# PFC_Interleaved_V8_1.net
KiCad netlist of a schematic drawn in Altium Designer
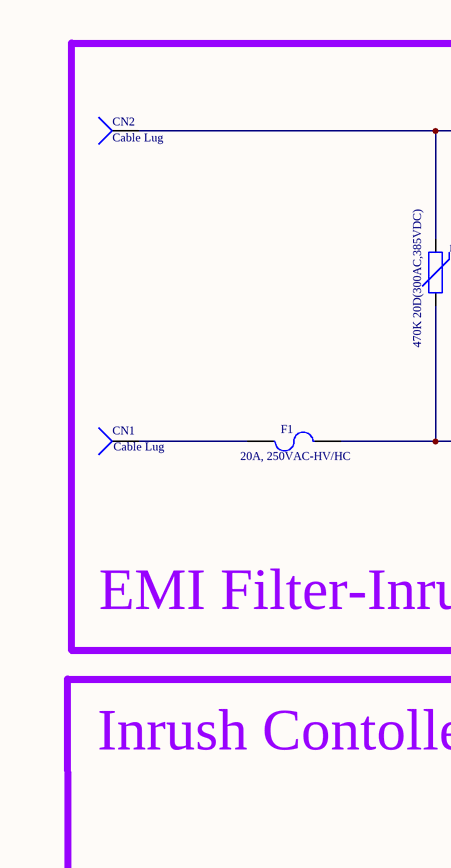
[diagram p0: PFC_Interleaved_V8.1.SchDoc, top left]
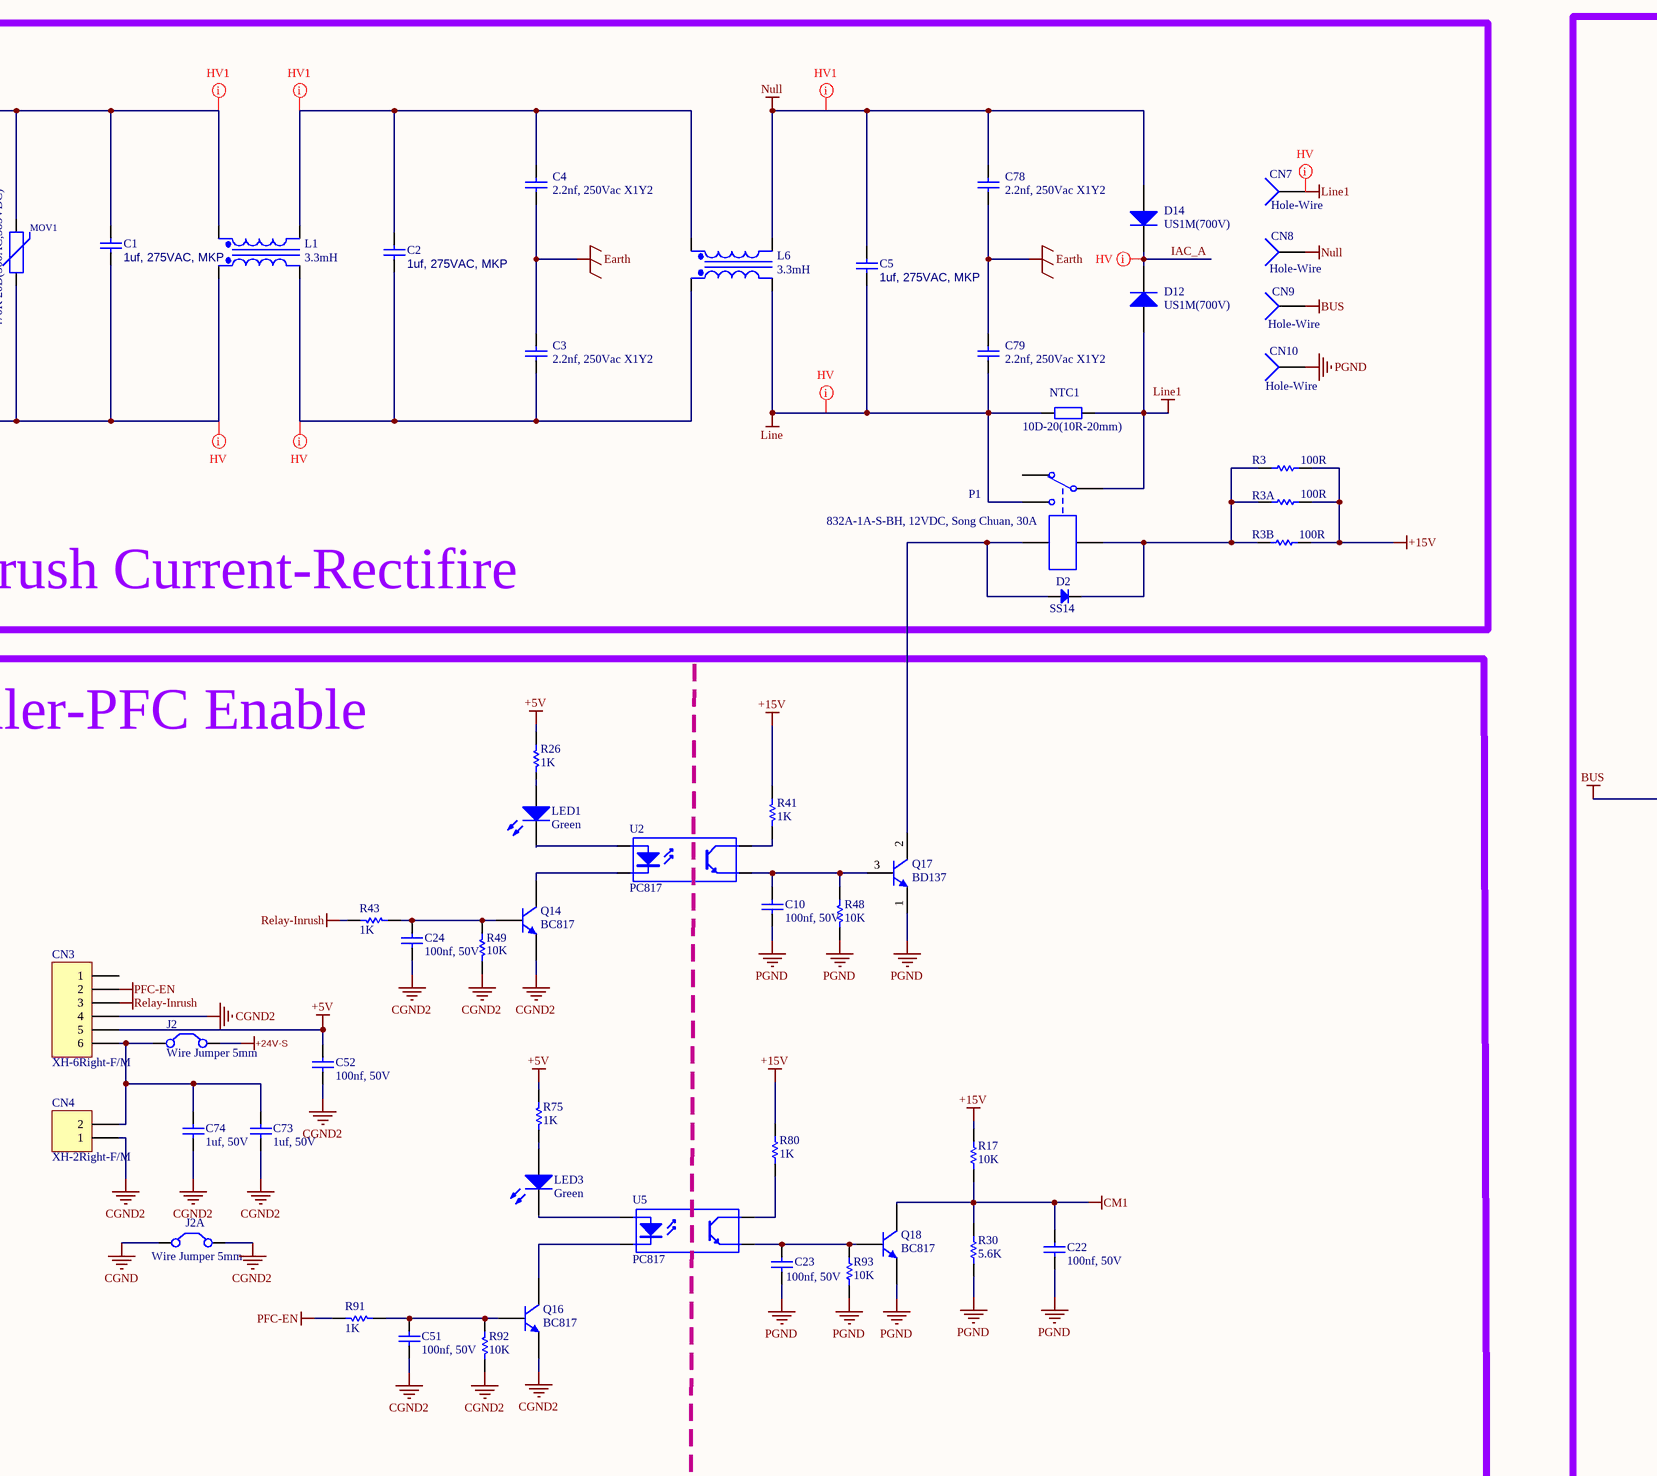
[diagram p1: PFC_Interleaved_V8.1.SchDoc, top middle]
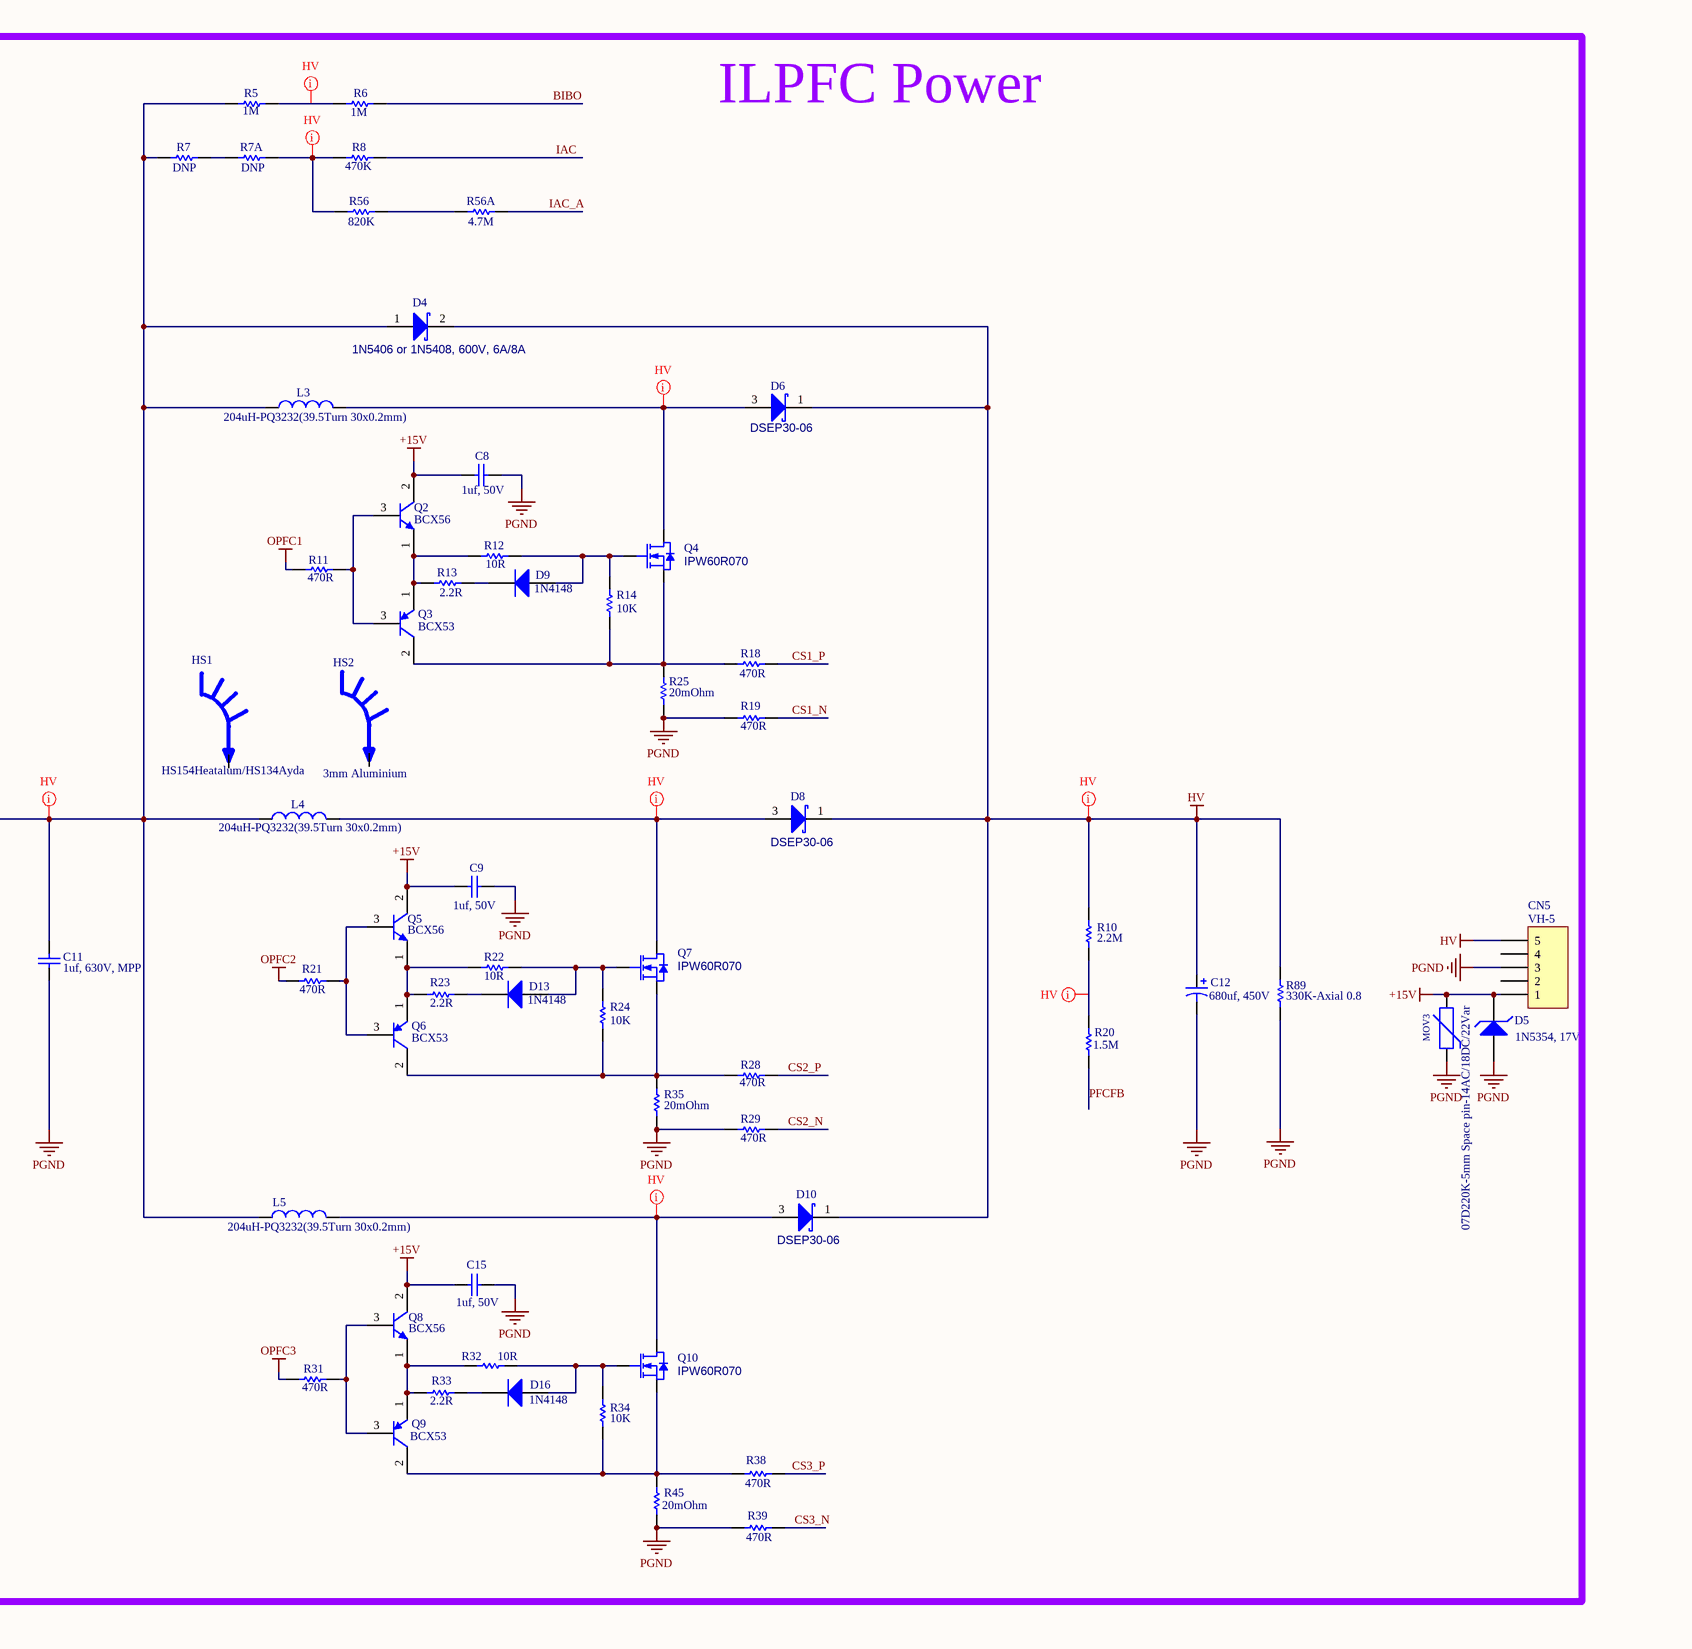
[diagram p2: PFC_Interleaved_V8.1.SchDoc, top right]
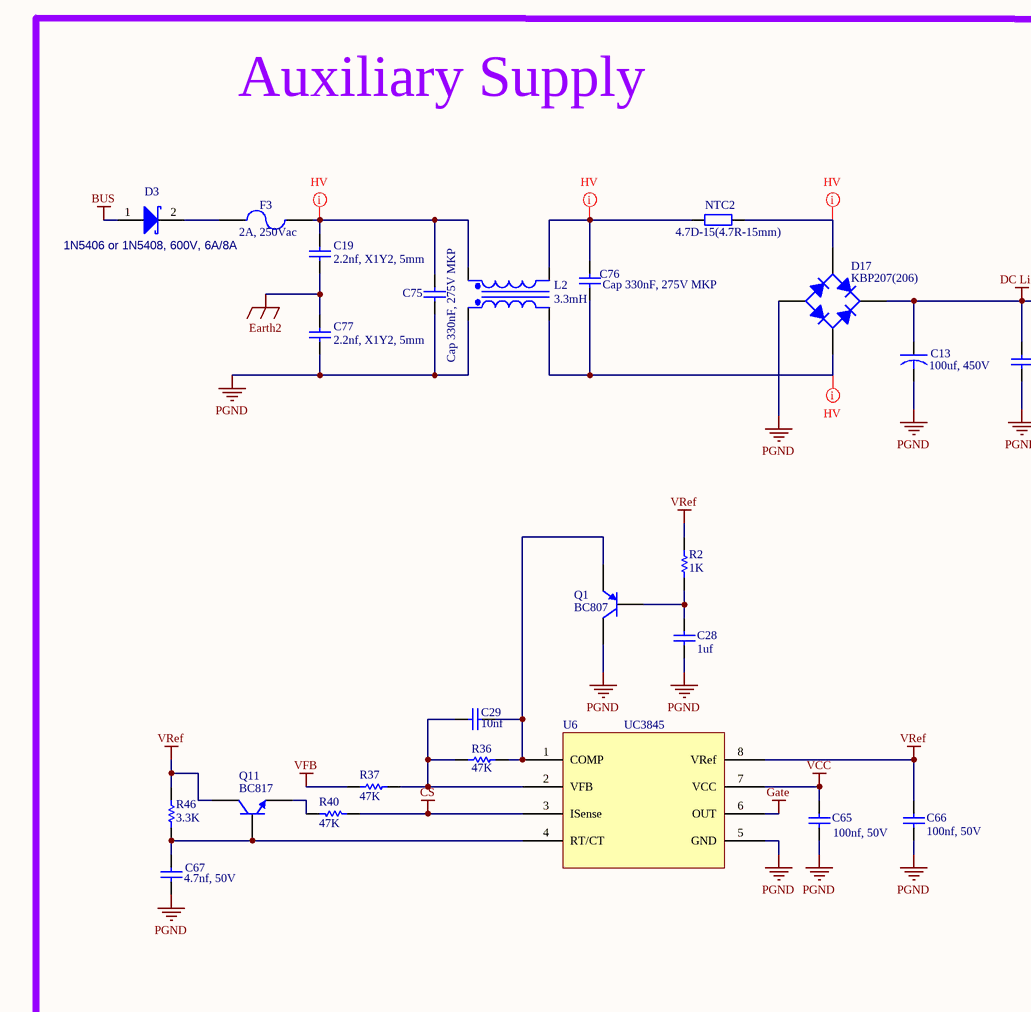
[diagram p3: PFC_Interleaved_V8.1.SchDoc, bottom left]
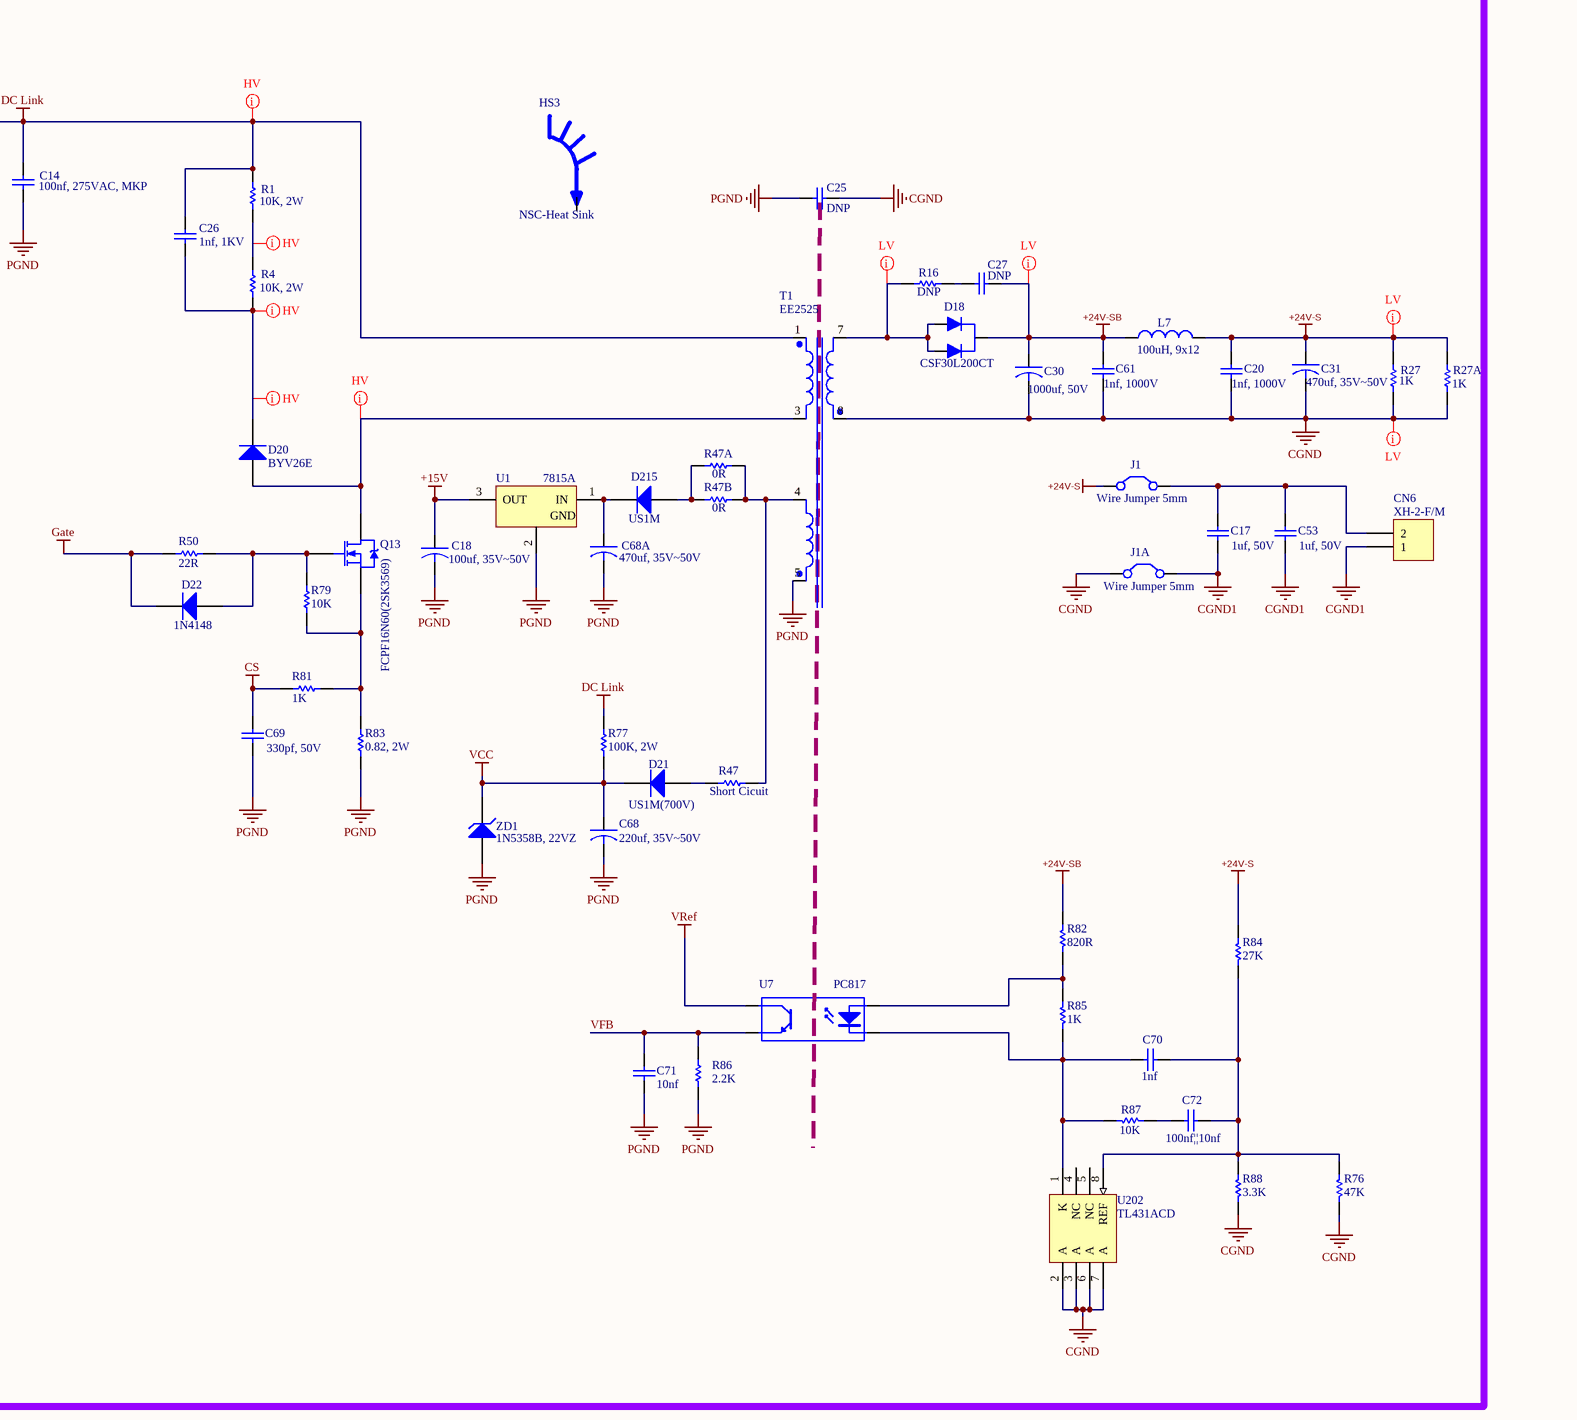
[diagram p4: PFC_Interleaved_V8.1.SchDoc, bottom middle]
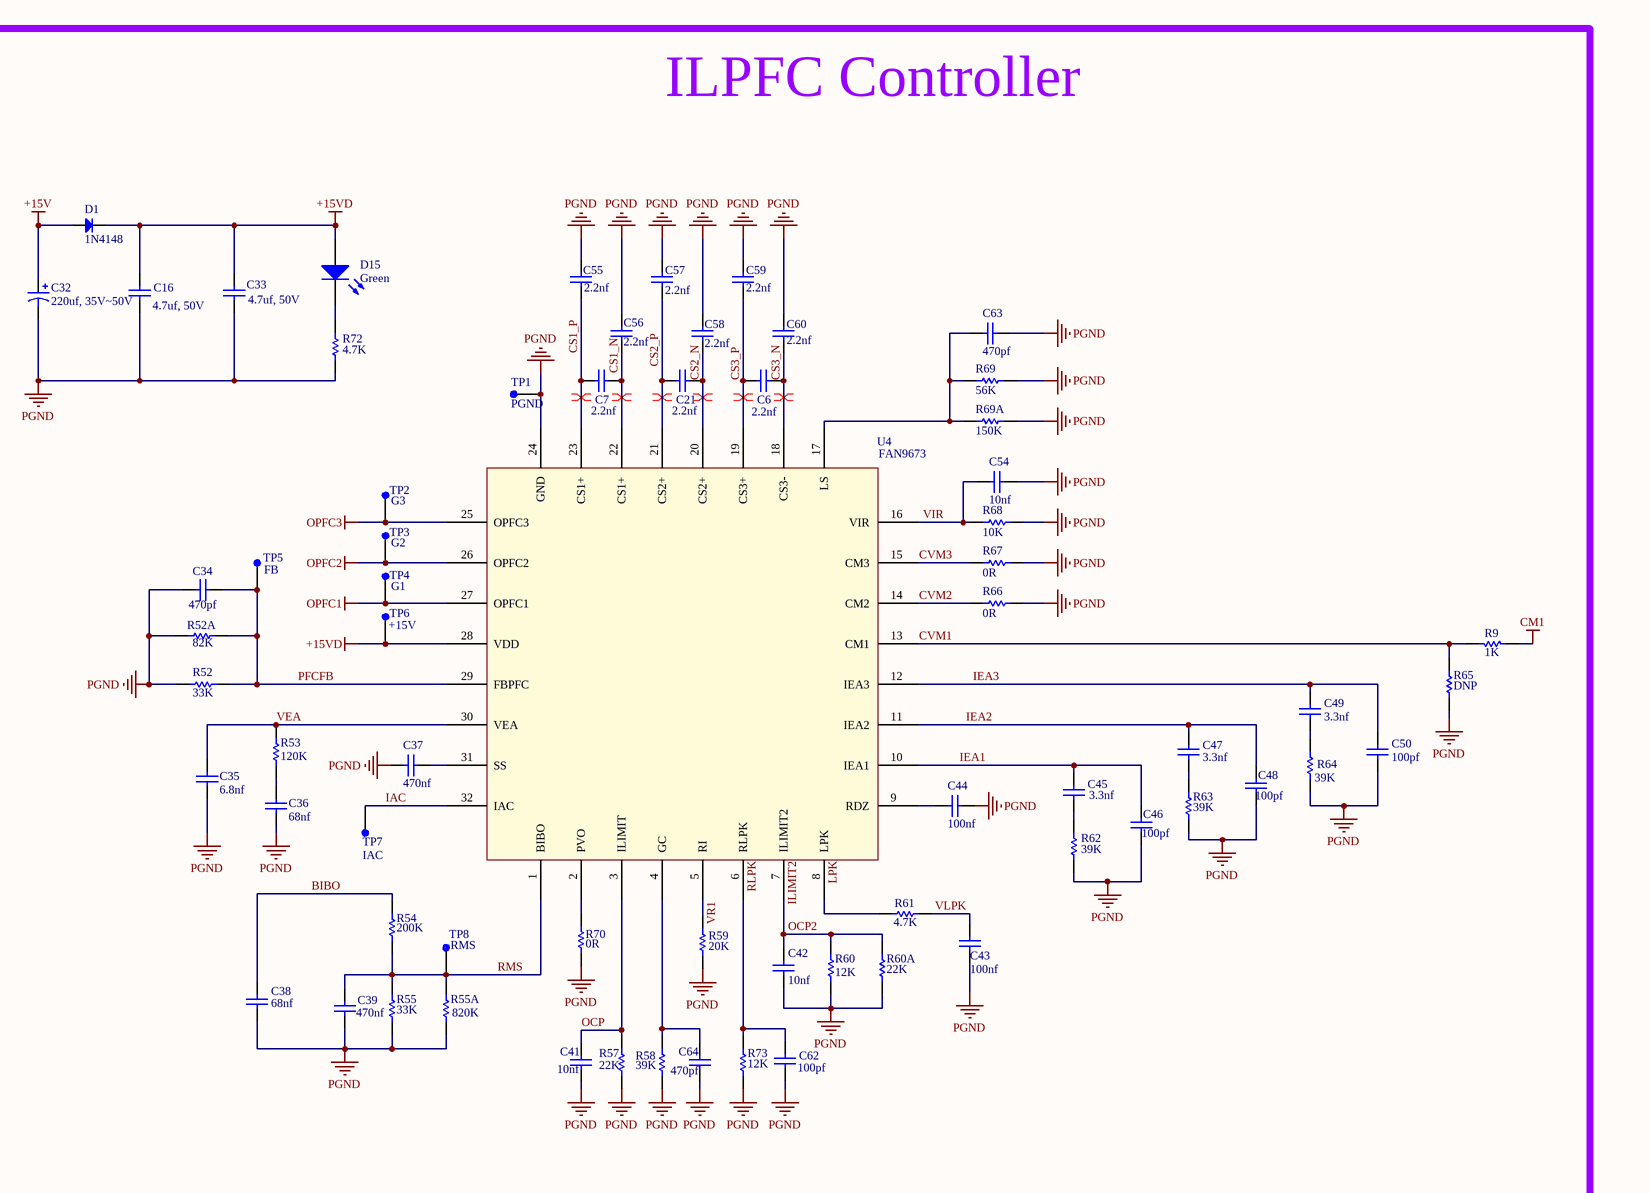
[diagram p5: PFC_Interleaved_V8.1.SchDoc, bottom right]

(export (version "E")
  (design (tool "Eeschema 10.0.6"))
  (components
    (comp (ref "C1")
      (value "1uf, 275VAC, MKP")
      (footprint "CAP-15mm-22mm-MKT-Qourum")
      (libsource (lib "PFC_Interleaved_V8.1") (part "ECQ-U2A474ML"))
    )
    (comp (ref "C2")
      (value "1uf, 275VAC, MKP")
      (footprint "CAP-15mm-22mm-MKT-Qourum")
      (libsource (lib "PFC_Interleaved_V8.1") (part "ECQ-U2A474ML"))
    )
    (comp (ref "C3")
      (value "2.2nf, 250Vac X1Y2")
      (footprint "CAP-RAD-7.5mm-PFC")
      (libsource (lib "altium-import") (part "root_1_DE2E3KY222MA2BM01_"))
    )
    (comp (ref "C4")
      (value "2.2nf, 250Vac X1Y2")
      (footprint "CAP-RAD-7.5mm-PFC")
      (libsource (lib "altium-import") (part "root_3_DE2E3KY222MA2BM01_"))
    )
    (comp (ref "C5")
      (value "1uf, 275VAC, MKP")
      (footprint "CAP-15mm-22mm-MKT-Qourum")
      (libsource (lib "PFC_Interleaved_V8.1") (part "ECQ-U2A474ML"))
    )
    (comp (ref "C6")
      (value "2.2nf")
      (footprint "C-0805")
      (libsource (lib "altium-import") (part "root_0_mirrored_DE2E3KY222MA2BM01_"))
    )
    (comp (ref "C7")
      (value "2.2nf")
      (footprint "C-0805")
      (libsource (lib "altium-import") (part "root_0_mirrored_DE2E3KY222MA2BM01_"))
    )
    (comp (ref "C8")
      (value "1uf, 50V")
      (footprint "C-0805")
      (libsource (lib "CAPACITOR") (part "Cap 0805(2)"))
    )
    (comp (ref "C9")
      (value "1uf, 50V")
      (footprint "C-0805")
      (libsource (lib "CAPACITOR") (part "Cap 0805(2)"))
    )
    (comp (ref "C10")
      (value "100nf, 50V")
      (footprint "C-0805")
      (libsource (lib "CAPACITOR") (part "Cap 0805(2)"))
    )
    (comp (ref "C11")
      (value "1uf, 630V, MPP")
      (footprint "CAP-15mm-22mm-MKT-Qourum-2")
      (libsource (lib "altium-import") (part "root_1_Cap Semi_"))
    )
    (comp (ref "C12")
      (value "680uf, 450V")
      (footprint "Cap-electrolytic-680uF-2")
      (libsource (lib "altium-import") (part "root_1_380LQ271M450K022_"))
    )
    (comp (ref "C13")
      (value "100uf, 450V")
      (footprint "Cap RAD7.5-16x35-2")
      (libsource (lib "*") (part "CAPACITOR"))
    )
    (comp (ref "C14")
      (value "100nf, 275VAC, MKP")
      (footprint "RAD-0.4-AUX")
      (libsource (lib "*") (part "Cap"))
    )
    (comp (ref "C15")
      (value "1uf, 50V")
      (footprint "C-0805")
      (libsource (lib "CAPACITOR") (part "Cap 0805(2)"))
    )
    (comp (ref "C16")
      (value "4.7uf, 50V")
      (footprint "C-1206")
      (libsource (lib "altium-import") (part "root_1_mirrored_DE2E3KY222MA2BM01_"))
    )
    (comp (ref "C17") (value "1uf, 50V") (footprint "C-0805") (libsource (lib "*") (part "Cap")))
    (comp (ref "C18")
      (value "100uf, 35V~50V")
      (footprint "Cap_Electrolytic5")
      (libsource (lib "*") (part "CAPACITOR"))
    )
    (comp (ref "C19")
      (value "2.2nf, X1Y2, 5mm")
      (footprint "Cap-TH-5mm")
      (libsource (lib "CAPACITOR") (part "Cap 0805(2)"))
    )
    (comp (ref "C20") (value "1nf, 1000V") (footprint "C-1206") (libsource (lib "*") (part "Cap")))
    (comp (ref "C21")
      (value "2.2nf")
      (footprint "C-0805")
      (libsource (lib "altium-import") (part "root_0_mirrored_DE2E3KY222MA2BM01_"))
    )
    (comp (ref "C22")
      (value "100nf, 50V")
      (footprint "C-0805")
      (libsource (lib "CAPACITOR") (part "Cap 0805(2)"))
    )
    (comp (ref "C23")
      (value "100nf, 50V")
      (footprint "C-0805")
      (libsource (lib "CAPACITOR") (part "Cap 0805(2)"))
    )
    (comp (ref "C24")
      (value "100nf, 50V")
      (footprint "C-0805")
      (libsource (lib "CAPACITOR") (part "Cap 0805(2)"))
    )
    (comp (ref "C25")
      (value "1nf, 1KV")
      (footprint "RAD-0.2-S-2")
      (fields (field (name "ASSEMBLY") "DNP"))
      (libsource (lib "Miscellaneous Devices") (part "Cap"))
    )
    (comp (ref "C26") (value "1nf, 1KV") (footprint "CAP RAD-0.2") (libsource (lib "*") (part "Cap")))
    (comp (ref "C27")
      (value "1nf, 1KV")
      (footprint "RAD-0.2-S-2")
      (fields (field (name "ASSEMBLY") "DNP"))
      (libsource (lib "Miscellaneous Devices") (part "Cap"))
    )
    (comp (ref "C28") (value "1uf") (footprint "C-0805") (libsource (lib "") (part "Cap_1")))
    (comp (ref "C29") (value "10nf") (footprint "C-0805") (libsource (lib "") (part "Cap_1")))
    (comp (ref "C30")
      (value "1000uf, 50V")
      (footprint "Cap-Elec-12mm*25mm")
      (libsource (lib "*") (part "CAPACITOR"))
    )
    (comp (ref "C31")
      (value "470uf, 35V~50V")
      (footprint "Cap_Electrolytic1")
      (libsource (lib "*") (part "CAPACITOR"))
    )
    (comp (ref "C32")
      (value "220uf, 35V~50V")
      (footprint "CAP-Elec-8mm*12mm")
      (libsource (lib "altium-import") (part "root_1_380LQ271M450K022_"))
    )
    (comp (ref "C33")
      (value "4.7uf, 50V")
      (footprint "C-1206")
      (libsource (lib "altium-import") (part "root_1_mirrored_DE2E3KY222MA2BM01_"))
    )
    (comp (ref "C34")
      (value "470pf")
      (footprint "C-0805")
      (libsource (lib "altium-import") (part "root_0_mirrored_DE2E3KY222MA2BM01_"))
    )
    (comp (ref "C35")
      (value "6.8nf")
      (footprint "C-0805")
      (libsource (lib "altium-import") (part "root_1_mirrored_DE2E3KY222MA2BM01_"))
    )
    (comp (ref "C36")
      (value "68nf")
      (footprint "C-0805")
      (libsource (lib "altium-import") (part "root_1_mirrored_DE2E3KY222MA2BM01_"))
    )
    (comp (ref "C37")
      (value "470nf")
      (footprint "C-0805")
      (libsource (lib "") (part "root_2_mirrored_DE2E3KY222MA2BM01__1"))
    )
    (comp (ref "C38")
      (value "68nf")
      (footprint "C-0805")
      (libsource (lib "altium-import") (part "root_3_mirrored_DE2E3KY222MA2BM01_"))
    )
    (comp (ref "C39")
      (value "470nf")
      (footprint "C-0805")
      (libsource (lib "altium-import") (part "root_3_mirrored_DE2E3KY222MA2BM01_"))
    )
    (comp (ref "C41")
      (value "10nf")
      (footprint "C-0805")
      (libsource (lib "altium-import") (part "root_3_mirrored_DE2E3KY222MA2BM01_"))
    )
    (comp (ref "C42")
      (value "10nf")
      (footprint "C-0805")
      (libsource (lib "altium-import") (part "root_3_mirrored_DE2E3KY222MA2BM01_"))
    )
    (comp (ref "C43")
      (value "100nf")
      (footprint "C-0805")
      (libsource (lib "altium-import") (part "root_3_mirrored_DE2E3KY222MA2BM01_"))
    )
    (comp (ref "C44")
      (value "100nf")
      (footprint "C-0805")
      (libsource (lib "altium-import") (part "root_2_mirrored_DE2E3KY222MA2BM01_"))
    )
    (comp (ref "C45")
      (value "3.3nf")
      (footprint "C-0805")
      (libsource (lib "altium-import") (part "root_3_mirrored_DE2E3KY222MA2BM01_"))
    )
    (comp (ref "C46")
      (value "100pf")
      (footprint "C-0805")
      (libsource (lib "altium-import") (part "root_3_mirrored_DE2E3KY222MA2BM01_"))
    )
    (comp (ref "C47")
      (value "3.3nf")
      (footprint "C-0805")
      (libsource (lib "altium-import") (part "root_3_mirrored_DE2E3KY222MA2BM01_"))
    )
    (comp (ref "C48")
      (value "100pf")
      (footprint "C-0805")
      (libsource (lib "altium-import") (part "root_3_mirrored_DE2E3KY222MA2BM01_"))
    )
    (comp (ref "C49")
      (value "3.3nf")
      (footprint "C-0805")
      (libsource (lib "altium-import") (part "root_3_mirrored_DE2E3KY222MA2BM01_"))
    )
    (comp (ref "C50")
      (value "100pf")
      (footprint "C-0805")
      (libsource (lib "altium-import") (part "root_3_mirrored_DE2E3KY222MA2BM01_"))
    )
    (comp (ref "C51")
      (value "100nf, 50V")
      (footprint "C-0805")
      (libsource (lib "CAPACITOR") (part "Cap 0805(2)"))
    )
    (comp (ref "C52")
      (value "100nf, 50V")
      (footprint "C-0805")
      (libsource (lib "CAPACITOR") (part "Cap 0805(2)"))
    )
    (comp (ref "C53") (value "1uf, 50V") (footprint "C-0805") (libsource (lib "*") (part "Cap")))
    (comp (ref "C54")
      (value "10nf")
      (footprint "C-0805")
      (libsource (lib "altium-import") (part "root_2_mirrored_DE2E3KY222MA2BM01_"))
    )
    (comp (ref "C55")
      (value "2.2nf")
      (footprint "C-0805")
      (libsource (lib "altium-import") (part "root_3_mirrored_DE2E3KY222MA2BM01_"))
    )
    (comp (ref "C56")
      (value "2.2nf")
      (footprint "C-0805")
      (libsource (lib "altium-import") (part "root_3_mirrored_DE2E3KY222MA2BM01_"))
    )
    (comp (ref "C57")
      (value "2.2nf")
      (footprint "C-0805")
      (libsource (lib "altium-import") (part "root_3_mirrored_DE2E3KY222MA2BM01_"))
    )
    (comp (ref "C58")
      (value "2.2nf")
      (footprint "C-0805")
      (libsource (lib "altium-import") (part "root_3_mirrored_DE2E3KY222MA2BM01_"))
    )
    (comp (ref "C59")
      (value "2.2nf")
      (footprint "C-0805")
      (libsource (lib "altium-import") (part "root_3_mirrored_DE2E3KY222MA2BM01_"))
    )
    (comp (ref "C60")
      (value "2.2nf")
      (footprint "C-0805")
      (libsource (lib "altium-import") (part "root_3_mirrored_DE2E3KY222MA2BM01_"))
    )
    (comp (ref "C61") (value "1nf, 1000V") (footprint "C-1206") (libsource (lib "*") (part "Cap")))
    (comp (ref "C62")
      (value "100pf")
      (footprint "C-0805")
      (libsource (lib "altium-import") (part "root_3_mirrored_DE2E3KY222MA2BM01_"))
    )
    (comp (ref "C63")
      (value "470pf")
      (footprint "C-0805")
      (libsource (lib "altium-import") (part "root_2_mirrored_DE2E3KY222MA2BM01_"))
    )
    (comp (ref "C64")
      (value "470pf")
      (footprint "C-0805")
      (libsource (lib "altium-import") (part "root_3_mirrored_DE2E3KY222MA2BM01_"))
    )
    (comp (ref "C65") (value "100nf, 50V") (footprint "C-0805") (libsource (lib "*") (part "Cap")))
    (comp (ref "C66") (value "100nf, 50V") (footprint "C-0805") (libsource (lib "*") (part "Cap")))
    (comp (ref "C67") (value "4.7nf, 50V") (footprint "C-0805") (libsource (lib "*") (part "Cap")))
    (comp (ref "C68")
      (value "220uf, 35V~50V")
      (footprint "CAP-Elec-8mm*12mm")
      (libsource (lib "*") (part "CAPACITOR"))
    )
    (comp (ref "C68A")
      (value "470uf, 35V~50V")
      (footprint "CAP-Elec-10mm*20mm")
      (libsource (lib "*") (part "CAPACITOR"))
    )
    (comp (ref "C69") (value "330pf, 50V") (footprint "R-0805") (libsource (lib "*") (part "Cap")))
    (comp (ref "C70")
      (value "1nf")
      (footprint "C-0805")
      (libsource (lib "Miscellaneous Devices") (part "Cap Semi"))
    )
    (comp (ref "C71") (value "10nf") (footprint "C-0805") (libsource (lib "") (part "Cap_1")))
    (comp (ref "C72")
      (value "100nfΖ10nf")
      (footprint "C-0805")
      (libsource (lib "Miscellaneous Devices") (part "Cap Semi"))
    )
    (comp (ref "C73") (value "1uf, 50V") (footprint "C-0805") (libsource (lib "*") (part "Cap")))
    (comp (ref "C74") (value "1uf, 50V") (footprint "C-0805") (libsource (lib "*") (part "Cap")))
    (comp (ref "C75")
      (value "Cap 330nF, 275V MKP")
      (footprint "Cap-X-2")
      (libsource (lib "CAPACITOR") (part "Cap 0805(2)"))
    )
    (comp (ref "C76")
      (value "Cap 330nF, 275V MKP")
      (footprint "Cap-X-2")
      (libsource (lib "CAPACITOR") (part "Cap 0805(2)"))
    )
    (comp (ref "C77")
      (value "2.2nf, X1Y2, 5mm")
      (footprint "Cap-TH-5mm")
      (libsource (lib "CAPACITOR") (part "Cap 0805(2)"))
    )
    (comp (ref "C78")
      (value "2.2nf, 250Vac X1Y2")
      (footprint "CAP-RAD-7.5mm-PFC")
      (libsource (lib "altium-import") (part "root_3_DE2E3KY222MA2BM01_"))
    )
    (comp (ref "C79")
      (value "2.2nf, 250Vac X1Y2")
      (footprint "CAP-RAD-7.5mm-PFC")
      (libsource (lib "altium-import") (part "root_1_DE2E3KY222MA2BM01_"))
    )
    (comp (ref "CN1")
      (value "Cable Lug")
      (footprint "Connector-Lug")
      (libsource (lib "Miscellaneous Connectors") (part "Socket"))
    )
    (comp (ref "CN2")
      (value "Cable Lug")
      (footprint "Connector-Lug")
      (libsource (lib "Miscellaneous Connectors") (part "Socket"))
    )
    (comp (ref "CN3")
      (value "XH-6Right-F/M")
      (footprint "Connector-XH-6")
      (libsource (lib "Miscellaneous Connectors") (part "Header 6"))
    )
    (comp (ref "CN4")
      (value "XH-2Right-F/M")
      (footprint "Connector-XH-2")
      (libsource (lib "Miscellaneous Connectors") (part "Header 2"))
    )
    (comp (ref "CN5")
      (value "VH-5")
      (footprint "PWL_5")
      (libsource (lib "Miscellaneous Connectors") (part "Header 5"))
    )
    (comp (ref "CN6")
      (value "XH-2-F/M")
      (footprint "Connector-XH-2")
      (libsource (lib "") (part "Header 2_1"))
    )
    (comp (ref "CN7")
      (value "Hole-Wire")
      (footprint "Connector-Lug-2")
      (libsource (lib "Miscellaneous Connectors") (part "Socket"))
    )
    (comp (ref "CN8")
      (value "Hole-Wire")
      (footprint "Connector-Lug-2")
      (libsource (lib "Miscellaneous Connectors") (part "Socket"))
    )
    (comp (ref "CN9")
      (value "Hole-Wire")
      (footprint "Connector-Lug-2")
      (libsource (lib "Miscellaneous Connectors") (part "Socket"))
    )
    (comp (ref "CN10")
      (value "Hole-Wire")
      (footprint "Connector-Lug-2")
      (libsource (lib "Miscellaneous Connectors") (part "Socket"))
    )
    (comp (ref "D1") (value "1N4148") (footprint "SOD-123-2") (libsource (lib "Flyback") (part "MUR460")))
    (comp (ref "D2") (value "SS14") (footprint "DO-214AC-SMA-2") (libsource (lib "Flyback") (part "MUR460")))
    (comp (ref "D3")
      (value "1N5406 or 1N5408, 600V, 6A/8A")
      (footprint "MUR460")
      (libsource (lib "") (part "DSEP30-06A_1"))
    )
    (comp (ref "D4")
      (value "1N5406 or 1N5408, 600V, 6A/8A")
      (footprint "MUR460")
      (libsource (lib "") (part "DSEP30-06A_1"))
    )
    (comp (ref "D5")
      (value "1N5354, 17V")
      (footprint "Diode-AXIAL-12mm-1200V")
      (libsource (lib "MCU-Lib") (part "Diode Zener Mini Melf"))
    )
    (comp (ref "D6")
      (value "DSEP30-06")
      (footprint "TO247-2Pin-PFC-HC")
      (libsource (lib "Flyback") (part "DSEP30-06A"))
    )
    (comp (ref "D8")
      (value "DSEP30-06")
      (footprint "TO247-2Pin-PFC-HC")
      (libsource (lib "Flyback") (part "DSEP30-06A"))
    )
    (comp (ref "D9")
      (value "1N4148")
      (footprint "SOD-123-2")
      (libsource (lib "Miscellaneous Devices") (part "Diode"))
    )
    (comp (ref "D10")
      (value "DSEP30-06")
      (footprint "TO247-2Pin-PFC-HC")
      (libsource (lib "Flyback") (part "DSEP30-06A"))
    )
    (comp (ref "D12")
      (value "US1M(700V)")
      (footprint "DO-214AC-SMA-2")
      (libsource (lib "Miscellaneous Devices") (part "Diode 1N4148"))
    )
    (comp (ref "D13")
      (value "1N4148")
      (footprint "SOD-123-2")
      (libsource (lib "Miscellaneous Devices") (part "Diode"))
    )
    (comp (ref "D14")
      (value "US1M(700V)")
      (footprint "DO-214AC-SMA-2")
      (libsource (lib "Miscellaneous Devices") (part "Diode 1N4148"))
    )
    (comp (ref "D15")
      (value "Green")
      (footprint "LED-0805")
      (libsource (lib "Miscellaneous Devices") (part "LED0"))
    )
    (comp (ref "D16")
      (value "1N4148")
      (footprint "SOD-123-2")
      (libsource (lib "Miscellaneous Devices") (part "Diode"))
    )
    (comp (ref "D17")
      (value "KBP207(206)")
      (footprint "DiodeBridge_KBP210")
      (libsource (lib "DIOD") (part "Bridge KBL"))
    )
    (comp (ref "D18")
      (value "CSF30L200CT")
      (footprint "TO220F-Bent-Leg")
      (libsource (lib "Flyback") (part "Diode MeanWell-1"))
    )
    (comp (ref "D20")
      (value "BYV26E")
      (footprint "Diode_Vertical3")
      (libsource (lib "Miscellaneous Devices") (part "Diode"))
    )
    (comp (ref "D21")
      (value "US1M(700V)")
      (footprint "DO-214AC-SMA-2")
      (libsource (lib "Miscellaneous Devices") (part "Diode"))
    )
    (comp (ref "D22")
      (value "1N4148")
      (footprint "SOD-123-2")
      (libsource (lib "Miscellaneous Devices") (part "Diode"))
    )
    (comp (ref "D215")
      (value "US1M")
      (footprint "DO-214AC-SMA-2")
      (libsource (lib "Miscellaneous Devices") (part "Diode"))
    )
    (comp (ref "F1")
      (value "20A, 250VAC-HV/HC")
      (footprint "Fuse 5x20_V2")
      (libsource (lib "Miscellaneous Devices") (part "Fuse 2"))
    )
    (comp (ref "F3")
      (value "2A, 250Vac")
      (footprint "Fuse Combination")
      (libsource (lib "") (part "Fuse 2_1"))
    )
    (comp (ref "HS1")
      (value "HS154Heatalum/HS134Ayda")
      (footprint "HeatSink-HC-1")
      (libsource (lib "Flyback") (part "HeatSink"))
    )
    (comp (ref "HS2")
      (value "3mm Aluminium")
      (footprint "HeatSink-HC--PFC-2")
      (libsource (lib "Flyback") (part "HeatSink"))
    )
    (comp (ref "HS3")
      (value "NSC-Heat Sink")
      (footprint "HeatSink12")
      (libsource (lib "Flyback") (part "HeatSink"))
    )
    (comp (ref "J1")
      (value "Wire Jumper 5mm")
      (footprint "Jumper-5mm")
      (libsource (lib "Flyback") (part "Jumper"))
    )
    (comp (ref "J1A")
      (value "Wire Jumper 5mm")
      (footprint "Jumper-5mm")
      (libsource (lib "Flyback") (part "Jumper"))
    )
    (comp (ref "J2")
      (value "Wire Jumper 5mm")
      (footprint "Jumper-5mm")
      (libsource (lib "Flyback") (part "Jumper"))
    )
    (comp (ref "J2A")
      (value "Wire Jumper 5mm")
      (footprint "Jumper-5mm")
      (libsource (lib "Flyback") (part "Jumper"))
    )
    (comp (ref "L1")
      (value "3.3mH")
      (footprint "Common Mode inductor-3")
      (libsource (lib "PFC_Interleaved_V8.1") (part "Trans Cupl"))
    )
    (comp (ref "L2")
      (value "3.3mH")
      (footprint "Trans line small-2")
      (libsource (lib "PFC_Interleaved_V8.1") (part "Trans Cupl"))
    )
    (comp (ref "L3")
      (value "204uH-PQ3232(39.5Turn 30x0.2mm)")
      (footprint "TRANS-PQ3535-2")
      (libsource (lib "Miscellaneous Devices") (part "Inductor"))
    )
    (comp (ref "L4")
      (value "204uH-PQ3232(39.5Turn 30x0.2mm)")
      (footprint "TRANS-PQ3535-4")
      (libsource (lib "Miscellaneous Devices") (part "Inductor"))
    )
    (comp (ref "L5")
      (value "204uH-PQ3232(39.5Turn 30x0.2mm)")
      (footprint "TRANS-PQ3535-6")
      (libsource (lib "Miscellaneous Devices") (part "Inductor"))
    )
    (comp (ref "L6")
      (value "3.3mH")
      (footprint "Common Mode inductor-3")
      (libsource (lib "") (part "Trans Cupl_1"))
    )
    (comp (ref "L7")
      (value "100uH, 9x12")
      (footprint "Inductor-Bar-P5-D10")
      (libsource (lib "") (part "Inductor_1"))
    )
    (comp (ref "LED1")
      (value "Green")
      (footprint "LED-0805")
      (libsource (lib "DIOD") (part "Diode LED1 SMD"))
    )
    (comp (ref "LED3")
      (value "Green")
      (footprint "LED-0805")
      (libsource (lib "DIOD") (part "Diode LED1 SMD"))
    )
    (comp (ref "MOV1")
      (value "470K 20D(300AC,385VDC)")
      (footprint "VDR-20D")
      (libsource (lib "altium-import") (part "root_1_B72207S2301K101_"))
    )
    (comp (ref "MOV3")
      (value "07D220K-5mm Space pin-14AC/18DC/22Var")
      (footprint "VAR-7D-5mm-1200V")
      (libsource (lib "altium-import") (part "root_3_mirrored_B72207S2301K101_"))
    )
    (comp (ref "NTC1")
      (value "10D-20(10R-20mm)")
      (footprint "VDR-20D")
      (libsource (lib "altium-import") (part "root_2_mirrored_Res2_"))
    )
    (comp (ref "NTC2")
      (value "4.7D-15(4.7R-15mm)")
      (footprint "NTC-8mm")
      (libsource (lib "altium-import") (part "root_2_mirrored_Res2_"))
    )
    (comp (ref "P1")
      (value "832A-1A-S-BH, 12VDC, Song Chuan, 30A")
      (footprint "832A1AS12VDCVDE-K")
      (libsource (lib "Miscellaneous Devices") (part "Relay-SPDT"))
    )
    (comp (ref "Q1") (value "BC807") (footprint "SOT-23") (libsource (lib "Flyback") (part "BCW68G")))
    (comp (ref "Q2")
      (value "BCX56")
      (footprint "SOT89L-K")
      (libsource (lib "Miscellaneous Devices") (part "BCX56"))
    )
    (comp (ref "Q3")
      (value "BCX53")
      (footprint "Flyback:SOT89L-K")
      (libsource (lib "Miscellaneous Devices") (part "BCX53"))
    )
    (comp (ref "Q4")
      (value "IPW60R070")
      (footprint "TO247-3Pin-PFC-HC-1")
      (libsource (lib "altium-import") (part "root_0_MOSFET N-CH_"))
    )
    (comp (ref "Q5")
      (value "BCX56")
      (footprint "SOT89L-K")
      (libsource (lib "Miscellaneous Devices") (part "BCX56"))
    )
    (comp (ref "Q6")
      (value "BCX53")
      (footprint "Flyback:SOT89L-K")
      (libsource (lib "Miscellaneous Devices") (part "BCX53"))
    )
    (comp (ref "Q7")
      (value "IPW60R070")
      (footprint "TO247-3Pin-PFC-HC-1")
      (libsource (lib "altium-import") (part "root_0_MOSFET N-CH_"))
    )
    (comp (ref "Q8")
      (value "BCX56")
      (footprint "SOT89L-K")
      (libsource (lib "Miscellaneous Devices") (part "BCX56"))
    )
    (comp (ref "Q9")
      (value "BCX53")
      (footprint "Flyback:SOT89L-K")
      (libsource (lib "Miscellaneous Devices") (part "BCX53"))
    )
    (comp (ref "Q10")
      (value "IPW60R070")
      (footprint "TO247-3Pin-PFC-HC-1")
      (libsource (lib "altium-import") (part "root_0_MOSFET N-CH_"))
    )
    (comp (ref "Q11")
      (value "BC817")
      (footprint "SOT-23")
      (libsource (lib "FSC Discrete BJT") (part "BC817-40"))
    )
    (comp (ref "Q13")
      (value "FCPF16N60(2SK3569)")
      (footprint "TO220F-Bent-Leg")
      (libsource (lib "IR Discrete MOSFET - Power") (part "IRF530N"))
    )
    (comp (ref "Q14")
      (value "BC817")
      (footprint "MSOT-23")
      (libsource (lib "FSC Discrete BJT") (part "BC817-40"))
    )
    (comp (ref "Q16")
      (value "BC817")
      (footprint "MSOT-23")
      (libsource (lib "FSC Discrete BJT") (part "BC817-40"))
    )
    (comp (ref "Q17") (value "BD137") (footprint "BD137-K") (libsource (lib "*") (part "BD137")))
    (comp (ref "Q18")
      (value "BC817")
      (footprint "MSOT-23")
      (libsource (lib "FSC Discrete BJT") (part "BC817-40"))
    )
    (comp (ref "R1")
      (value "10K, 2W")
      (footprint "Resistor_Vertical3")
      (libsource (lib "Miscellaneous Devices") (part "Res1"))
    )
    (comp (ref "R2")
      (value "1K")
      (footprint "R-0805")
      (libsource (lib "Miscellaneous Devices") (part "Res1"))
    )
    (comp (ref "R3")
      (value "100R")
      (footprint "R-1206")
      (libsource (lib "Miscellaneous Devices") (part "Res1"))
    )
    (comp (ref "R3A")
      (value "100R")
      (footprint "R-1206")
      (libsource (lib "Miscellaneous Devices") (part "Res1"))
    )
    (comp (ref "R3B")
      (value "100R")
      (footprint "R-1206")
      (libsource (lib "Miscellaneous Devices") (part "Res1"))
    )
    (comp (ref "R4")
      (value "10K, 2W")
      (footprint "Resistor_Vertical3")
      (libsource (lib "Miscellaneous Devices") (part "Res1"))
    )
    (comp (ref "R5")
      (value "1M")
      (footprint "R-1206")
      (libsource (lib "Miscellaneous Devices") (part "Res1"))
    )
    (comp (ref "R6")
      (value "1M")
      (footprint "R-1206")
      (libsource (lib "Miscellaneous Devices") (part "Res1"))
    )
    (comp (ref "R7")
      (value "6M")
      (footprint "R-1206")
      (fields (field (name "ASSEMBLY") "DNP"))
      (libsource (lib "Miscellaneous Devices") (part "Res1"))
    )
    (comp (ref "R7A")
      (value "0R")
      (footprint "R-1206")
      (fields (field (name "ASSEMBLY") "DNP"))
      (libsource (lib "Miscellaneous Devices") (part "Res1"))
    )
    (comp (ref "R8")
      (value "470K")
      (footprint "R-1206")
      (libsource (lib "Miscellaneous Devices") (part "Res1"))
    )
    (comp (ref "R9")
      (value "1K")
      (footprint "R-0805")
      (libsource (lib "Miscellaneous Devices") (part "Res1"))
    )
    (comp (ref "R10")
      (value "2.2M")
      (footprint "R-1206")
      (libsource (lib "Miscellaneous Devices") (part "Res1"))
    )
    (comp (ref "R11")
      (value "470R")
      (footprint "R-0805")
      (libsource (lib "Miscellaneous Devices") (part "Res1"))
    )
    (comp (ref "R12")
      (value "10R")
      (footprint "R-0805")
      (libsource (lib "Miscellaneous Devices") (part "Res1"))
    )
    (comp (ref "R13")
      (value "2.2R")
      (footprint "R-0805")
      (libsource (lib "Miscellaneous Devices") (part "Res1"))
    )
    (comp (ref "R14")
      (value "10K")
      (footprint "R-0805")
      (libsource (lib "Miscellaneous Devices") (part "Res1"))
    )
    (comp (ref "R16")
      (value "10R")
      (footprint "R-1206")
      (fields (field (name "ASSEMBLY") "DNP"))
      (libsource (lib "Miscellaneous Devices") (part "Res1"))
    )
    (comp (ref "R17")
      (value "10K")
      (footprint "R-0805")
      (libsource (lib "Miscellaneous Devices") (part "Res1"))
    )
    (comp (ref "R18")
      (value "470R")
      (footprint "R-0805")
      (libsource (lib "Miscellaneous Devices") (part "Res1"))
    )
    (comp (ref "R19")
      (value "470R")
      (footprint "R-0805")
      (libsource (lib "Miscellaneous Devices") (part "Res1"))
    )
    (comp (ref "R20")
      (value "1.5M")
      (footprint "R-1206")
      (libsource (lib "Miscellaneous Devices") (part "Res1"))
    )
    (comp (ref "R21")
      (value "470R")
      (footprint "R-0805")
      (libsource (lib "Miscellaneous Devices") (part "Res1"))
    )
    (comp (ref "R22")
      (value "10R")
      (footprint "R-0805")
      (libsource (lib "Miscellaneous Devices") (part "Res1"))
    )
    (comp (ref "R23")
      (value "2.2R")
      (footprint "R-0805")
      (libsource (lib "Miscellaneous Devices") (part "Res1"))
    )
    (comp (ref "R24")
      (value "10K")
      (footprint "R-0805")
      (libsource (lib "Miscellaneous Devices") (part "Res1"))
    )
    (comp (ref "R25")
      (value "20mOhm")
      (footprint "R-2512")
      (libsource (lib "Miscellaneous Devices") (part "Res1"))
    )
    (comp (ref "R26")
      (value "1K")
      (footprint "R-0805")
      (libsource (lib "Miscellaneous Devices") (part "Res1"))
    )
    (comp (ref "R27")
      (value "1K")
      (footprint "R-1206")
      (libsource (lib "Miscellaneous Devices") (part "Res1"))
    )
    (comp (ref "R27A")
      (value "1K")
      (footprint "R-1206")
      (libsource (lib "Miscellaneous Devices") (part "Res1"))
    )
    (comp (ref "R28")
      (value "470R")
      (footprint "R-0805")
      (libsource (lib "Miscellaneous Devices") (part "Res1"))
    )
    (comp (ref "R29")
      (value "470R")
      (footprint "R-0805")
      (libsource (lib "Miscellaneous Devices") (part "Res1"))
    )
    (comp (ref "R30")
      (value "5.6K")
      (footprint "R-0805")
      (libsource (lib "Miscellaneous Devices") (part "Res1"))
    )
    (comp (ref "R31")
      (value "470R")
      (footprint "R-0805")
      (libsource (lib "Miscellaneous Devices") (part "Res1"))
    )
    (comp (ref "R32")
      (value "10R")
      (footprint "R-0805")
      (libsource (lib "Miscellaneous Devices") (part "Res1"))
    )
    (comp (ref "R33")
      (value "2.2R")
      (footprint "R-0805")
      (libsource (lib "Miscellaneous Devices") (part "Res1"))
    )
    (comp (ref "R34")
      (value "10K")
      (footprint "R-0805")
      (libsource (lib "Miscellaneous Devices") (part "Res1"))
    )
    (comp (ref "R35")
      (value "20mOhm")
      (footprint "R-2512")
      (libsource (lib "Miscellaneous Devices") (part "Res1"))
    )
    (comp (ref "R36")
      (value "47K")
      (footprint "R-0805")
      (libsource (lib "Miscellaneous Devices") (part "Res1"))
    )
    (comp (ref "R37")
      (value "47K")
      (footprint "R-0805")
      (libsource (lib "Miscellaneous Devices") (part "Res1"))
    )
    (comp (ref "R38")
      (value "470R")
      (footprint "R-0805")
      (libsource (lib "Miscellaneous Devices") (part "Res1"))
    )
    (comp (ref "R39")
      (value "470R")
      (footprint "R-0805")
      (libsource (lib "Miscellaneous Devices") (part "Res1"))
    )
    (comp (ref "R40")
      (value "47K")
      (footprint "R-0805")
      (libsource (lib "Miscellaneous Devices") (part "Res1"))
    )
    (comp (ref "R41")
      (value "1K")
      (footprint "R-0805")
      (libsource (lib "Miscellaneous Devices") (part "Res1"))
    )
    (comp (ref "R43")
      (value "1K")
      (footprint "R-0805")
      (libsource (lib "Miscellaneous Devices") (part "Res1"))
    )
    (comp (ref "R45")
      (value "20mOhm")
      (footprint "R-2512")
      (libsource (lib "Miscellaneous Devices") (part "Res1"))
    )
    (comp (ref "R46")
      (value "3.3K")
      (footprint "R-0805")
      (libsource (lib "Miscellaneous Devices") (part "Res1"))
    )
    (comp (ref "R47")
      (value "Short Cicuit")
      (footprint "R-1206")
      (libsource (lib "Miscellaneous Devices") (part "Res1"))
    )
    (comp (ref "R47A")
      (value "0R")
      (footprint "R-1206")
      (libsource (lib "Miscellaneous Devices") (part "Res1"))
    )
    (comp (ref "R47B")
      (value "0R")
      (footprint "R-1206")
      (libsource (lib "Miscellaneous Devices") (part "Res1"))
    )
    (comp (ref "R48")
      (value "10K")
      (footprint "R-0805")
      (libsource (lib "Miscellaneous Devices") (part "Res1"))
    )
    (comp (ref "R49")
      (value "10K")
      (footprint "R-0805")
      (libsource (lib "Miscellaneous Devices") (part "Res1"))
    )
    (comp (ref "R50")
      (value "22R")
      (footprint "R-0805")
      (libsource (lib "Miscellaneous Devices") (part "Res1"))
    )
    (comp (ref "R52")
      (value "33K")
      (footprint "R-0805")
      (libsource (lib "Miscellaneous Devices") (part "Res1"))
    )
    (comp (ref "R52A")
      (value "82K")
      (footprint "R-0805")
      (libsource (lib "Miscellaneous Devices") (part "Res1"))
    )
    (comp (ref "R53")
      (value "120K")
      (footprint "R-0805")
      (libsource (lib "Miscellaneous Devices") (part "Res1"))
    )
    (comp (ref "R54")
      (value "200K")
      (footprint "R-1206")
      (libsource (lib "Miscellaneous Devices") (part "Res1"))
    )
    (comp (ref "R55")
      (value "33K")
      (footprint "R-0805")
      (libsource (lib "Miscellaneous Devices") (part "Res1"))
    )
    (comp (ref "R55A")
      (value "820K")
      (footprint "R-0805")
      (libsource (lib "Miscellaneous Devices") (part "Res1"))
    )
    (comp (ref "R56")
      (value "820K")
      (footprint "R-1206")
      (libsource (lib "Miscellaneous Devices") (part "Res1"))
    )
    (comp (ref "R56A")
      (value "4.7M")
      (footprint "R-1206")
      (libsource (lib "Miscellaneous Devices") (part "Res1"))
    )
    (comp (ref "R57")
      (value "22K")
      (footprint "R-0805")
      (libsource (lib "Miscellaneous Devices") (part "Res1"))
    )
    (comp (ref "R58")
      (value "39K")
      (footprint "R-0805")
      (libsource (lib "Miscellaneous Devices") (part "Res1"))
    )
    (comp (ref "R59")
      (value "20K")
      (footprint "R-0805")
      (libsource (lib "Miscellaneous Devices") (part "Res1"))
    )
    (comp (ref "R60")
      (value "12K")
      (footprint "R-0805")
      (libsource (lib "Miscellaneous Devices") (part "Res1"))
    )
    (comp (ref "R60A")
      (value "22K")
      (footprint "R-0805")
      (libsource (lib "Miscellaneous Devices") (part "Res1"))
    )
    (comp (ref "R61")
      (value "4.7K")
      (footprint "R-0805")
      (libsource (lib "Miscellaneous Devices") (part "Res1"))
    )
    (comp (ref "R62")
      (value "39K")
      (footprint "R-0805")
      (libsource (lib "Miscellaneous Devices") (part "Res1"))
    )
    (comp (ref "R63")
      (value "39K")
      (footprint "R-0805")
      (libsource (lib "Miscellaneous Devices") (part "Res1"))
    )
    (comp (ref "R64")
      (value "39K")
      (footprint "R-0805")
      (libsource (lib "Miscellaneous Devices") (part "Res1"))
    )
    (comp (ref "R65")
      (value "0R")
      (footprint "R-0805")
      (fields (field (name "ASSEMBLY") "DNP"))
      (libsource (lib "Miscellaneous Devices") (part "Res1"))
    )
    (comp (ref "R66")
      (value "0R")
      (footprint "R-0805")
      (libsource (lib "Miscellaneous Devices") (part "Res1"))
    )
    (comp (ref "R67")
      (value "0R")
      (footprint "R-0805")
      (libsource (lib "Miscellaneous Devices") (part "Res1"))
    )
    (comp (ref "R68")
      (value "10K")
      (footprint "R-0805")
      (libsource (lib "Miscellaneous Devices") (part "Res1"))
    )
    (comp (ref "R69")
      (value "56K")
      (footprint "R-0805")
      (libsource (lib "Miscellaneous Devices") (part "Res1"))
    )
    (comp (ref "R69A")
      (value "150K")
      (footprint "R-0805")
      (libsource (lib "Miscellaneous Devices") (part "Res1"))
    )
    (comp (ref "R70")
      (value "0R")
      (footprint "R-0805")
      (libsource (lib "Miscellaneous Devices") (part "Res1"))
    )
    (comp (ref "R72")
      (value "4.7K")
      (footprint "R-0805")
      (libsource (lib "Miscellaneous Devices") (part "Res1"))
    )
    (comp (ref "R73")
      (value "12K")
      (footprint "R-0805")
      (libsource (lib "Miscellaneous Devices") (part "Res1"))
    )
    (comp (ref "R75")
      (value "1K")
      (footprint "R-0805")
      (libsource (lib "Miscellaneous Devices") (part "Res1"))
    )
    (comp (ref "R76")
      (value "47K")
      (footprint "R-0805")
      (libsource (lib "Miscellaneous Devices") (part "Res1"))
    )
    (comp (ref "R77")
      (value "100K, 2W")
      (footprint "Resistor_Vertical3")
      (libsource (lib "Miscellaneous Devices") (part "Res1"))
    )
    (comp (ref "R79")
      (value "10K")
      (footprint "R-0805")
      (libsource (lib "Miscellaneous Devices") (part "Res1"))
    )
    (comp (ref "R80")
      (value "1K")
      (footprint "R-0805")
      (libsource (lib "Miscellaneous Devices") (part "Res1"))
    )
    (comp (ref "R81")
      (value "1K")
      (footprint "R-0805")
      (libsource (lib "Miscellaneous Devices") (part "Res1"))
    )
    (comp (ref "R82")
      (value "820R")
      (footprint "R-0805")
      (libsource (lib "Miscellaneous Devices") (part "Res1"))
    )
    (comp (ref "R83")
      (value "0.82, 2W")
      (footprint "Resistor_Vertical3")
      (libsource (lib "Miscellaneous Devices") (part "Res1"))
    )
    (comp (ref "R84")
      (value "27K")
      (footprint "R-0805")
      (libsource (lib "Miscellaneous Devices") (part "Res1"))
    )
    (comp (ref "R85")
      (value "1K")
      (footprint "R-0805")
      (libsource (lib "Miscellaneous Devices") (part "Res1"))
    )
    (comp (ref "R86")
      (value "2.2K")
      (footprint "R-0805")
      (libsource (lib "Miscellaneous Devices") (part "Res1"))
    )
    (comp (ref "R87")
      (value "10K")
      (footprint "R-0805")
      (libsource (lib "Miscellaneous Devices") (part "Res1"))
    )
    (comp (ref "R88")
      (value "3.3K")
      (footprint "R-0805")
      (libsource (lib "Miscellaneous Devices") (part "Res1"))
    )
    (comp (ref "R89")
      (value "330K-Axial 0.8")
      (footprint "Res DC Link  axial 0.6")
      (libsource (lib "Miscellaneous Devices") (part "Res Semi"))
    )
    (comp (ref "R91")
      (value "1K")
      (footprint "R-0805")
      (libsource (lib "Miscellaneous Devices") (part "Res1"))
    )
    (comp (ref "R92")
      (value "10K")
      (footprint "R-0805")
      (libsource (lib "Miscellaneous Devices") (part "Res1"))
    )
    (comp (ref "R93")
      (value "10K")
      (footprint "R-0805")
      (libsource (lib "Miscellaneous Devices") (part "Res1"))
    )
    (comp (ref "T1")
      (value "EE2525")
      (footprint "EE2525_Comb4")
      (libsource (lib "Flyback") (part "flyback-ILPFC-2"))
    )
    (comp (ref "TP1") (value "PGND") (footprint "Test-Point") (libsource (lib "Flyback") (part "TEST POINT")))
    (comp (ref "TP2") (value "G3") (footprint "Test-Point") (libsource (lib "Flyback") (part "TEST POINT")))
    (comp (ref "TP3") (value "G2") (footprint "Test-Point") (libsource (lib "Flyback") (part "TEST POINT")))
    (comp (ref "TP4") (value "G1") (footprint "Test-Point") (libsource (lib "Flyback") (part "TEST POINT")))
    (comp (ref "TP5") (value "FB") (footprint "Test-Point") (libsource (lib "Flyback") (part "TEST POINT")))
    (comp (ref "TP6") (value "+15V") (footprint "Test-Point") (libsource (lib "Flyback") (part "TEST POINT")))
    (comp (ref "TP7") (value "IAC") (footprint "Test-Point") (libsource (lib "Flyback") (part "TEST POINT")))
    (comp (ref "TP8") (value "RMS") (footprint "Test-Point") (libsource (lib "Flyback") (part "TEST POINT")))
    (comp (ref "U1")
      (value "7815A")
      (footprint "TO220F-Bent-Leg")
      (libsource (lib "ON Semi Power Mgt Voltage Regulator") (part "MC7808CT"))
    )
    (comp (ref "U2") (value "PC817") (footprint "DIP_4") (libsource (lib "Schlib1") (part "TLP521")))
    (comp (ref "U4")
      (value "FAN9673")
      (footprint "LQFP-32-FAN9673")
      (libsource (lib "Flyback") (part "FAN9673"))
    )
    (comp (ref "U5") (value "PC817") (footprint "DIP_4") (libsource (lib "Schlib1") (part "TLP521")))
    (comp (ref "U6")
      (value "UC3845")
      (footprint "Flyback:So-8-W-L-fly")
      (libsource (lib "Flyback") (part "UC3842"))
    )
    (comp (ref "U7") (value "PC817") (footprint "DIP_4") (libsource (lib "Schlib1") (part "TLP521")))
    (comp (ref "U202")
      (value "TL431ACD")
      (footprint "so8+sot23")
      (libsource (lib "ON Semi Power Mgt Voltage Reference") (part "TL431ACD"))
    )
    (comp (ref "ZD1")
      (value "1N5358B, 22VZ")
      (footprint "Diode_Vertical3")
      (libsource (lib "Miscellaneous Devices") (part "D Zener"))
    )
  )
  (nets
    (net (code "1") (name "+5V") (class "Default")
      (node (ref "C52") (pin "1") (pinfunction "1_1") (pintype "passive"))
      (node (ref "CN3") (pin "5") (pinfunction "5_5") (pintype "passive"))
      (node (ref "R26") (pin "2") (pinfunction "2_2") (pintype "passive"))
      (node (ref "R75") (pin "2") (pinfunction "2_2") (pintype "passive"))
    )
    (net (code "2") (name "+15V") (class "Default")
      (node (ref "C15") (pin "1") (pinfunction "1_1") (pintype "passive"))
      (node (ref "C18") (pin "1") (pinfunction "1_1") (pintype "passive"))
      (node (ref "C32") (pin "1") (pinfunction "+_1") (pintype "passive"))
      (node (ref "C8") (pin "1") (pinfunction "1_1") (pintype "passive"))
      (node (ref "C9") (pin "1") (pinfunction "1_1") (pintype "passive"))
      (node (ref "CN5") (pin "1") (pinfunction "1_1") (pintype "passive"))
      (node (ref "D1") (pin "1") (pinfunction "A_1") (pintype "passive"))
      (node (ref "D5") (pin "2") (pinfunction "K_2") (pintype "passive"))
      (node (ref "MOV3") (pin "1") (pinfunction "1_1") (pintype "passive"))
      (node (ref "Q2") (pin "2") (pinfunction "C_2") (pintype "passive"))
      (node (ref "Q5") (pin "2") (pinfunction "C_2") (pintype "passive"))
      (node (ref "Q8") (pin "2") (pinfunction "C_2") (pintype "passive"))
      (node (ref "R17") (pin "1") (pinfunction "1_1") (pintype "passive"))
      (node (ref "R3") (pin "2") (pinfunction "2_2") (pintype "passive"))
      (node (ref "R3A") (pin "2") (pinfunction "2_2") (pintype "passive"))
      (node (ref "R3B") (pin "2") (pinfunction "2_2") (pintype "passive"))
      (node (ref "R41") (pin "2") (pinfunction "2_2") (pintype "passive"))
      (node (ref "R80") (pin "1") (pinfunction "1_1") (pintype "passive"))
      (node (ref "U1") (pin "3") (pinfunction "OUT_3") (pintype "power_in"))
    )
    (net (code "3") (name "+15VD") (class "Default")
      (node (ref "C16") (pin "2") (pinfunction "2_2") (pintype "passive"))
      (node (ref "C33") (pin "2") (pinfunction "2_2") (pintype "passive"))
      (node (ref "D1") (pin "2") (pinfunction "K_2") (pintype "passive"))
      (node (ref "D15") (pin "1") (pinfunction "A_1") (pintype "passive"))
      (node (ref "TP6") (pin "1") (pintype "passive"))
      (node (ref "U4") (pin "28") (pinfunction "VDD_28") (pintype "passive"))
    )
    (net (code "4") (name "+24V-S") (class "Default")
      (node (ref "C20") (pin "2") (pinfunction "2_2") (pintype "passive"))
      (node (ref "C31") (pin "1") (pinfunction "1_1") (pintype "passive"))
      (node (ref "J1") (pin "1") (pinfunction "C1_1") (pintype "passive"))
      (node (ref "J2") (pin "1") (pinfunction "C1_1") (pintype "passive"))
      (node (ref "L7") (pin "2") (pinfunction "2_2") (pintype "passive"))
      (node (ref "R27") (pin "2") (pinfunction "2_2") (pintype "passive"))
      (node (ref "R27A") (pin "2") (pinfunction "2_2") (pintype "passive"))
      (node (ref "R84") (pin "2") (pinfunction "2_2") (pintype "passive"))
    )
    (net (code "5") (name "+24V-SB") (class "Default")
      (node (ref "C27") (pin "1") (pinfunction "1_1") (pintype "passive"))
      (node (ref "C30") (pin "1") (pinfunction "1_1") (pintype "passive"))
      (node (ref "C61") (pin "2") (pinfunction "2_2") (pintype "passive"))
      (node (ref "D18") (pin "2") (pinfunction "K_2") (pintype "passive"))
      (node (ref "L7") (pin "1") (pinfunction "1_1") (pintype "passive"))
      (node (ref "R82") (pin "2") (pinfunction "2_2") (pintype "passive"))
    )
    (net (code "6") (name "/BIBO") (class "Default")
      (node (ref "C38") (pin "2") (pinfunction "2_2") (pintype "passive"))
      (node (ref "R54") (pin "1") (pinfunction "1_1") (pintype "passive"))
      (node (ref "R6") (pin "1") (pinfunction "1_1") (pintype "passive"))
    )
    (net (code "7") (name "/CS1_N") (class "Default")
      (node (ref "C56") (pin "1") (pinfunction "1_1") (pintype "passive"))
      (node (ref "C7") (pin "1") (pinfunction "1_1") (pintype "passive"))
      (node (ref "R19") (pin "1") (pinfunction "1_1") (pintype "passive"))
      (node (ref "U4") (pin "22") (pinfunction "CS1+_22") (pintype "passive"))
    )
    (net (code "8") (name "/CS1_P") (class "Default")
      (node (ref "C55") (pin "1") (pinfunction "1_1") (pintype "passive"))
      (node (ref "C7") (pin "2") (pinfunction "2_2") (pintype "passive"))
      (node (ref "R18") (pin "1") (pinfunction "1_1") (pintype "passive"))
      (node (ref "U4") (pin "23") (pinfunction "CS1+_23") (pintype "passive"))
    )
    (net (code "9") (name "/CS2_N") (class "Default")
      (node (ref "C21") (pin "1") (pinfunction "1_1") (pintype "passive"))
      (node (ref "C58") (pin "1") (pinfunction "1_1") (pintype "passive"))
      (node (ref "R29") (pin "1") (pinfunction "1_1") (pintype "passive"))
      (node (ref "U4") (pin "20") (pinfunction "CS2+_20") (pintype "passive"))
    )
    (net (code "10") (name "/CS2_P") (class "Default")
      (node (ref "C21") (pin "2") (pinfunction "2_2") (pintype "passive"))
      (node (ref "C57") (pin "1") (pinfunction "1_1") (pintype "passive"))
      (node (ref "R28") (pin "1") (pinfunction "1_1") (pintype "passive"))
      (node (ref "U4") (pin "21") (pinfunction "CS2+_21") (pintype "passive"))
    )
    (net (code "11") (name "/CS3_N") (class "Default")
      (node (ref "C6") (pin "1") (pinfunction "1_1") (pintype "passive"))
      (node (ref "C60") (pin "1") (pinfunction "1_1") (pintype "passive"))
      (node (ref "R39") (pin "1") (pinfunction "1_1") (pintype "passive"))
      (node (ref "U4") (pin "18") (pinfunction "CS3-_18") (pintype "passive"))
    )
    (net (code "12") (name "/CS3_P") (class "Default")
      (node (ref "C59") (pin "1") (pinfunction "1_1") (pintype "passive"))
      (node (ref "C6") (pin "2") (pinfunction "2_2") (pintype "passive"))
      (node (ref "R38") (pin "1") (pinfunction "1_1") (pintype "passive"))
      (node (ref "U4") (pin "19") (pinfunction "CS3+_19") (pintype "passive"))
    )
    (net (code "13") (name "/CVM1") (class "Default")
      (node (ref "R65") (pin "2") (pinfunction "2_2") (pintype "passive"))
      (node (ref "R9") (pin "1") (pinfunction "1_1") (pintype "passive"))
      (node (ref "U4") (pin "13") (pinfunction "CM1_13") (pintype "passive"))
    )
    (net (code "14") (name "/CVM2") (class "Default")
      (node (ref "R66") (pin "2") (pinfunction "2_2") (pintype "passive"))
      (node (ref "U4") (pin "14") (pinfunction "CM2_14") (pintype "passive"))
    )
    (net (code "15") (name "/CVM3") (class "Default")
      (node (ref "R67") (pin "2") (pinfunction "2_2") (pintype "passive"))
      (node (ref "U4") (pin "15") (pinfunction "CM3_15") (pintype "passive"))
    )
    (net (code "16") (name "/IAC") (class "Default")
      (node (ref "R8") (pin "1") (pinfunction "1_1") (pintype "passive"))
      (node (ref "TP7") (pin "1") (pintype "passive"))
      (node (ref "U4") (pin "32") (pinfunction "IAC_32") (pintype "passive"))
    )
    (net (code "17") (name "/IAC_A") (class "Default")
      (node (ref "D12") (pin "2") (pinfunction "K_2") (pintype "passive"))
      (node (ref "D14") (pin "2") (pinfunction "K_2") (pintype "passive"))
      (node (ref "R56A") (pin "1") (pinfunction "1_1") (pintype "passive"))
    )
    (net (code "18") (name "/IEA1") (class "Default")
      (node (ref "C45") (pin "2") (pinfunction "2_2") (pintype "passive"))
      (node (ref "C46") (pin "2") (pinfunction "2_2") (pintype "passive"))
      (node (ref "U4") (pin "10") (pinfunction "IEA1_10") (pintype "passive"))
    )
    (net (code "19") (name "/IEA2") (class "Default")
      (node (ref "C47") (pin "2") (pinfunction "2_2") (pintype "passive"))
      (node (ref "C48") (pin "2") (pinfunction "2_2") (pintype "passive"))
      (node (ref "U4") (pin "11") (pinfunction "IEA2_11") (pintype "passive"))
    )
    (net (code "20") (name "/IEA3") (class "Default")
      (node (ref "C49") (pin "2") (pinfunction "2_2") (pintype "passive"))
      (node (ref "C50") (pin "2") (pinfunction "2_2") (pintype "passive"))
      (node (ref "U4") (pin "12") (pinfunction "IEA3_12") (pintype "passive"))
    )
    (net (code "23") (name "/OCP") (class "Default")
      (node (ref "C41") (pin "2") (pinfunction "2_2") (pintype "passive"))
      (node (ref "R57") (pin "1") (pinfunction "1_1") (pintype "passive"))
      (node (ref "U4") (pin "3") (pinfunction "ILIMIT_3") (pintype "passive"))
    )
    (net (code "24") (name "/OCP2") (class "Default")
      (node (ref "C42") (pin "2") (pinfunction "2_2") (pintype "passive"))
      (node (ref "R60") (pin "1") (pinfunction "1_1") (pintype "passive"))
      (node (ref "R60A") (pin "1") (pinfunction "1_1") (pintype "passive"))
      (node (ref "U4") (pin "7") (pinfunction "ILIMIT2_7") (pintype "passive"))
    )
    (net (code "25") (name "/PFCFB") (class "Default")
      (node (ref "C34") (pin "1") (pinfunction "1_1") (pintype "passive"))
      (node (ref "R20") (pin "1") (pinfunction "1_1") (pintype "passive"))
      (node (ref "R52") (pin "2") (pinfunction "2_2") (pintype "passive"))
      (node (ref "R52A") (pin "2") (pinfunction "2_2") (pintype "passive"))
      (node (ref "TP5") (pin "1") (pintype "passive"))
      (node (ref "U4") (pin "29") (pinfunction "FBPFC_29") (pintype "passive"))
    )
    (net (code "27") (name "/RMS") (class "Default")
      (node (ref "C39") (pin "2") (pinfunction "2_2") (pintype "passive"))
      (node (ref "R54") (pin "2") (pinfunction "2_2") (pintype "passive"))
      (node (ref "R55") (pin "1") (pinfunction "1_1") (pintype "passive"))
      (node (ref "R55A") (pin "1") (pinfunction "1_1") (pintype "passive"))
      (node (ref "TP8") (pin "1") (pintype "passive"))
      (node (ref "U4") (pin "1") (pinfunction "BIBO_1") (pintype "passive"))
    )
    (net (code "28") (name "/VEA") (class "Default")
      (node (ref "C35") (pin "2") (pinfunction "2_2") (pintype "passive"))
      (node (ref "R53") (pin "2") (pinfunction "2_2") (pintype "passive"))
      (node (ref "U4") (pin "30") (pinfunction "VEA_30") (pintype "passive"))
    )
    (net (code "29") (name "/VIR") (class "Default")
      (node (ref "C54") (pin "2") (pinfunction "2_2") (pintype "passive"))
      (node (ref "R68") (pin "2") (pinfunction "2_2") (pintype "passive"))
      (node (ref "U4") (pin "16") (pinfunction "VIR_16") (pintype "passive"))
    )
    (net (code "30") (name "/VLPK") (class "Default")
      (node (ref "C43") (pin "2") (pinfunction "2_2") (pintype "passive"))
      (node (ref "R61") (pin "2") (pinfunction "2_2") (pintype "passive"))
    )
    (net (code "31") (name "/VR1") (class "Default")
      (node (ref "R59") (pin "1") (pinfunction "1_1") (pintype "passive"))
      (node (ref "U4") (pin "5") (pinfunction "RI_5") (pintype "passive"))
    )
    (net (code "32") (name "BUS") (class "Default")
      (node (ref "C11") (pin "2") (pinfunction "2_2") (pintype "passive"))
      (node (ref "CN9") (pin "1") (pinfunction "1_1") (pintype "passive"))
      (node (ref "D3") (pin "1") (pintype "passive"))
      (node (ref "D4") (pin "1") (pintype "passive"))
      (node (ref "L3") (pin "2") (pinfunction "2_2") (pintype "passive"))
      (node (ref "L4") (pin "2") (pinfunction "2_2") (pintype "passive"))
      (node (ref "L5") (pin "2") (pinfunction "2_2") (pintype "passive"))
      (node (ref "R5") (pin "2") (pinfunction "2_2") (pintype "passive"))
      (node (ref "R7") (pin "2") (pinfunction "2_2") (pintype "passive"))
    )
    (net (code "33") (name "CGND") (class "Default")
      (node (ref "C20") (pin "1") (pinfunction "1_1") (pintype "passive"))
      (node (ref "C25") (pin "1") (pinfunction "1_1") (pintype "passive"))
      (node (ref "C30") (pin "2") (pinfunction "2_2") (pintype "passive"))
      (node (ref "C31") (pin "2") (pinfunction "2_2") (pintype "passive"))
      (node (ref "C61") (pin "1") (pinfunction "1_1") (pintype "passive"))
      (node (ref "J1A") (pin "2") (pinfunction "C2_2") (pintype "passive"))
      (node (ref "J2A") (pin "2") (pinfunction "C2_2") (pintype "passive"))
      (node (ref "R27") (pin "1") (pinfunction "1_1") (pintype "passive"))
      (node (ref "R27A") (pin "1") (pinfunction "1_1") (pintype "passive"))
      (node (ref "R76") (pin "1") (pinfunction "1_1") (pintype "passive"))
      (node (ref "R88") (pin "1") (pinfunction "1_1") (pintype "passive"))
      (node (ref "T1") (pin "8") (pintype "passive"))
      (node (ref "U202") (pin "2") (pinfunction "A_2") (pintype "passive"))
      (node (ref "U202") (pin "3") (pinfunction "A_3") (pintype "passive"))
      (node (ref "U202") (pin "6") (pinfunction "A_6") (pintype "passive"))
      (node (ref "U202") (pin "7") (pinfunction "A_7") (pintype "passive"))
    )
    (net (code "34") (name "CGND1") (class "Default")
      (node (ref "C17") (pin "1") (pinfunction "1_1") (pintype "passive"))
      (node (ref "C53") (pin "1") (pinfunction "1_1") (pintype "passive"))
      (node (ref "CN6") (pin "1") (pinfunction "1_1") (pintype "passive"))
      (node (ref "J1A") (pin "1") (pinfunction "C1_1") (pintype "passive"))
    )
    (net (code "35") (name "CGND2") (class "Default")
      (node (ref "C24") (pin "2") (pinfunction "2_2") (pintype "passive"))
      (node (ref "C51") (pin "2") (pinfunction "2_2") (pintype "passive"))
      (node (ref "C52") (pin "2") (pinfunction "2_2") (pintype "passive"))
      (node (ref "C73") (pin "1") (pinfunction "1_1") (pintype "passive"))
      (node (ref "C74") (pin "1") (pinfunction "1_1") (pintype "passive"))
      (node (ref "CN3") (pin "4") (pinfunction "4_4") (pintype "passive"))
      (node (ref "CN4") (pin "1") (pinfunction "1_1") (pintype "passive"))
      (node (ref "J2A") (pin "1") (pinfunction "C1_1") (pintype "passive"))
      (node (ref "Q14") (pin "2") (pinfunction "E_2") (pintype "passive"))
      (node (ref "Q16") (pin "2") (pinfunction "E_2") (pintype "passive"))
      (node (ref "R49") (pin "2") (pinfunction "2_2") (pintype "passive"))
      (node (ref "R92") (pin "2") (pinfunction "2_2") (pintype "passive"))
    )
    (net (code "36") (name "CM1") (class "Default")
      (node (ref "C22") (pin "1") (pinfunction "1_1") (pintype "passive"))
      (node (ref "Q18") (pin "3") (pinfunction "C_3") (pintype "passive"))
      (node (ref "R17") (pin "2") (pinfunction "2_2") (pintype "passive"))
      (node (ref "R30") (pin "1") (pinfunction "1_1") (pintype "passive"))
      (node (ref "R9") (pin "2") (pinfunction "2_2") (pintype "passive"))
    )
    (net (code "37") (name "CS") (class "Default")
      (node (ref "C69") (pin "2") (pinfunction "2_2") (pintype "passive"))
      (node (ref "R40") (pin "1") (pinfunction "1_1") (pintype "passive"))
      (node (ref "R81") (pin "1") (pinfunction "1_1") (pintype "passive"))
      (node (ref "U6") (pin "3") (pinfunction "ISense_3") (pintype "passive"))
    )
    (net (code "38") (name "DC Link") (class "Default")
      (node (ref "C13") (pin "1") (pinfunction "1_1") (pintype "passive"))
      (node (ref "C14") (pin "2") (pinfunction "2_2") (pintype "passive"))
      (node (ref "C26") (pin "2") (pinfunction "2_2") (pintype "passive"))
      (node (ref "D17") (pin "1") (pinfunction "K_1") (pintype "passive"))
      (node (ref "R1") (pin "1") (pinfunction "1_1") (pintype "passive"))
      (node (ref "R77") (pin "1") (pinfunction "1_1") (pintype "passive"))
      (node (ref "T1") (pin "1") (pintype "passive"))
    )
    (net (code "39") (name "Earth") (class "Default")
      (node (ref "C3") (pin "1") (pinfunction "1_1") (pintype "passive"))
      (node (ref "C4") (pin "1") (pinfunction "1_1") (pintype "passive"))
      (node (ref "C78") (pin "1") (pinfunction "1_1") (pintype "passive"))
      (node (ref "C79") (pin "1") (pinfunction "1_1") (pintype "passive"))
    )
    (net (code "40") (name "Earth2") (class "Default")
      (node (ref "C19") (pin "1") (pinfunction "1_1") (pintype "passive"))
      (node (ref "C77") (pin "2") (pinfunction "2_2") (pintype "passive"))
    )
    (net (code "41") (name "Gate") (class "Default")
      (node (ref "D22") (pin "2") (pinfunction "K_2") (pintype "passive"))
      (node (ref "R50") (pin "2") (pinfunction "2_2") (pintype "passive"))
      (node (ref "U6") (pin "6") (pinfunction "OUT_6") (pintype "passive"))
    )
    (net (code "42") (name "HV") (class "Default")
      (node (ref "C12") (pin "1") (pinfunction "+_1") (pintype "passive"))
      (node (ref "CN5") (pin "5") (pinfunction "5_5") (pintype "passive"))
      (node (ref "D10") (pin "1") (pintype "passive"))
      (node (ref "D4") (pin "2") (pintype "passive"))
      (node (ref "D6") (pin "1") (pintype "passive"))
      (node (ref "D8") (pin "1") (pintype "passive"))
      (node (ref "R10") (pin "2") (pinfunction "2_2") (pintype "passive"))
      (node (ref "R89") (pin "2") (pinfunction "2_2") (pintype "passive"))
    )
    (net (code "43") (name "Line") (class "Default")
      (node (ref "C5") (pin "2") (pinfunction "2_2") (pintype "passive"))
      (node (ref "C79") (pin "2") (pinfunction "2_2") (pintype "passive"))
      (node (ref "L6") (pin "2") (pinfunction "Pri-_2") (pintype "passive"))
      (node (ref "NTC1") (pin "1") (pinfunction "1_1") (pintype "passive"))
      (node (ref "P1") (pin "2") (pinfunction "3_2") (pintype "passive"))
    )
    (net (code "44") (name "Line1") (class "Default")
      (node (ref "CN7") (pin "1") (pinfunction "1_1") (pintype "passive"))
      (node (ref "D12") (pin "1") (pinfunction "A_1") (pintype "passive"))
      (node (ref "NTC1") (pin "2") (pinfunction "2_2") (pintype "passive"))
      (node (ref "P1") (pin "3") (pinfunction "1_3") (pintype "passive"))
    )
    (net (code "45") (name "Net-(C27-Pad2)") (class "Default")
      (node (ref "C27") (pin "2") (pinfunction "2_2") (pintype "passive"))
      (node (ref "R16") (pin "1") (pinfunction "1_1") (pintype "passive"))
    )
    (net (code "46") (name "Net-(C36-Pad2)") (class "Default")
      (node (ref "C36") (pin "2") (pinfunction "2_2") (pintype "passive"))
      (node (ref "R53") (pin "1") (pinfunction "1_1") (pintype "passive"))
    )
    (net (code "47") (name "Net-(C45-Pad1)") (class "Default")
      (node (ref "C45") (pin "1") (pinfunction "1_1") (pintype "passive"))
      (node (ref "R62") (pin "2") (pinfunction "2_2") (pintype "passive"))
    )
    (net (code "48") (name "Net-(C47-Pad1)") (class "Default")
      (node (ref "C47") (pin "1") (pinfunction "1_1") (pintype "passive"))
      (node (ref "R63") (pin "2") (pinfunction "2_2") (pintype "passive"))
    )
    (net (code "49") (name "Net-(C49-Pad1)") (class "Default")
      (node (ref "C49") (pin "1") (pinfunction "1_1") (pintype "passive"))
      (node (ref "R64") (pin "2") (pinfunction "2_2") (pintype "passive"))
    )
    (net (code "50") (name "Net-(C72-Pad1)") (class "Default")
      (node (ref "C72") (pin "1") (pinfunction "1_1") (pintype "passive"))
      (node (ref "R87") (pin "2") (pinfunction "2_2") (pintype "passive"))
    )
    (net (code "51") (name "Net-(CN1-Pad1)") (class "Default")
      (node (ref "CN1") (pin "1") (pinfunction "1_1") (pintype "passive"))
      (node (ref "F1") (pin "1") (pinfunction "1_1") (pintype "passive"))
    )
    (net (code "52") (name "Net-(D2-A)") (class "Default")
      (node (ref "D2") (pin "1") (pinfunction "A_1") (pintype "passive"))
      (node (ref "P1") (pin "4") (pinfunction "5_4") (pintype "passive"))
      (node (ref "Q17") (pin "2") (pinfunction "C_2") (pintype "passive"))
    )
    (net (code "53") (name "Net-(D2-K)") (class "Default")
      (node (ref "D2") (pin "2") (pinfunction "K_2") (pintype "passive"))
      (node (ref "P1") (pin "5") (pinfunction "4_5") (pintype "passive"))
      (node (ref "R3") (pin "1") (pinfunction "1_1") (pintype "passive"))
      (node (ref "R3A") (pin "1") (pinfunction "1_1") (pintype "passive"))
      (node (ref "R3B") (pin "1") (pinfunction "1_1") (pintype "passive"))
    )
    (net (code "54") (name "Net-(D3-Pad2)") (class "Default")
      (node (ref "D3") (pin "2") (pintype "passive"))
      (node (ref "F3") (pin "1") (pinfunction "1_1") (pintype "passive"))
    )
    (net (code "55") (name "Net-(D9-A)") (class "Default")
      (node (ref "D9") (pin "1") (pinfunction "A_1") (pintype "passive"))
      (node (ref "Q4") (pin "1") (pinfunction "G_1") (pintype "passive"))
      (node (ref "R12") (pin "1") (pinfunction "1_1") (pintype "passive"))
      (node (ref "R14") (pin "2") (pinfunction "2_2") (pintype "passive"))
    )
    (net (code "56") (name "Net-(D9-K)") (class "Default")
      (node (ref "D9") (pin "2") (pinfunction "K_2") (pintype "passive"))
      (node (ref "R13") (pin "2") (pinfunction "2_2") (pintype "passive"))
    )
    (net (code "57") (name "Net-(D13-A)") (class "Default")
      (node (ref "D13") (pin "1") (pinfunction "A_1") (pintype "passive"))
      (node (ref "Q7") (pin "1") (pinfunction "G_1") (pintype "passive"))
      (node (ref "R22") (pin "1") (pinfunction "1_1") (pintype "passive"))
      (node (ref "R24") (pin "2") (pinfunction "2_2") (pintype "passive"))
    )
    (net (code "58") (name "Net-(D13-K)") (class "Default")
      (node (ref "D13") (pin "2") (pinfunction "K_2") (pintype "passive"))
      (node (ref "R23") (pin "2") (pinfunction "2_2") (pintype "passive"))
    )
    (net (code "59") (name "Net-(D15-K)") (class "Default")
      (node (ref "D15") (pin "2") (pinfunction "K_2") (pintype "passive"))
      (node (ref "R72") (pin "2") (pinfunction "2_2") (pintype "passive"))
    )
    (net (code "60") (name "Net-(D16-A)") (class "Default")
      (node (ref "D16") (pin "1") (pinfunction "A_1") (pintype "passive"))
      (node (ref "Q10") (pin "1") (pinfunction "G_1") (pintype "passive"))
      (node (ref "R32") (pin "1") (pinfunction "1_1") (pintype "passive"))
      (node (ref "R34") (pin "2") (pinfunction "2_2") (pintype "passive"))
    )
    (net (code "61") (name "Net-(D16-K)") (class "Default")
      (node (ref "D16") (pin "2") (pinfunction "K_2") (pintype "passive"))
      (node (ref "R33") (pin "2") (pinfunction "2_2") (pintype "passive"))
    )
    (net (code "62") (name "Net-(D17-C-Pad2)") (class "Default")
      (node (ref "D17") (pin "2") (pinfunction "C_2") (pintype "passive"))
      (node (ref "NTC2") (pin "2") (pinfunction "2_2") (pintype "passive"))
    )
    (net (code "63") (name "Net-(D18-A1)") (class "Default")
      (node (ref "D18") (pin "1") (pinfunction "A1_1") (pintype "passive"))
      (node (ref "D18") (pin "3") (pinfunction "A2_3") (pintype "passive"))
      (node (ref "R16") (pin "2") (pinfunction "2_2") (pintype "passive"))
      (node (ref "T1") (pin "7") (pintype "passive"))
    )
    (net (code "64") (name "Net-(D20-A)") (class "Default")
      (node (ref "D20") (pin "1") (pinfunction "A_1") (pintype "passive"))
      (node (ref "Q13") (pin "2") (pinfunction "D_2") (pintype "passive"))
      (node (ref "T1") (pin "3") (pintype "passive"))
    )
    (net (code "65") (name "Net-(D20-K)") (class "Default")
      (node (ref "C26") (pin "1") (pinfunction "1_1") (pintype "passive"))
      (node (ref "D20") (pin "2") (pinfunction "K_2") (pintype "passive"))
      (node (ref "R4") (pin "1") (pinfunction "1_1") (pintype "passive"))
    )
    (net (code "66") (name "Net-(D21-A)") (class "Default")
      (node (ref "D21") (pin "1") (pinfunction "A_1") (pintype "passive"))
      (node (ref "R47") (pin "2") (pinfunction "2_2") (pintype "passive"))
    )
    (net (code "67") (name "Net-(D22-A)") (class "Default")
      (node (ref "D22") (pin "1") (pinfunction "A_1") (pintype "passive"))
      (node (ref "Q13") (pin "1") (pinfunction "G_1") (pintype "passive"))
      (node (ref "R50") (pin "1") (pinfunction "1_1") (pintype "passive"))
      (node (ref "R79") (pin "1") (pinfunction "1_1") (pintype "passive"))
    )
    (net (code "68") (name "Net-(D215-A)") (class "Default")
      (node (ref "D215") (pin "1") (pinfunction "A_1") (pintype "passive"))
      (node (ref "R47A") (pin "2") (pinfunction "2_2") (pintype "passive"))
      (node (ref "R47B") (pin "2") (pinfunction "2_2") (pintype "passive"))
    )
    (net (code "69") (name "Net-(D215-K)") (class "Default")
      (node (ref "C68A") (pin "1") (pinfunction "1_1") (pintype "passive"))
      (node (ref "D215") (pin "2") (pinfunction "K_2") (pintype "passive"))
      (node (ref "U1") (pin "1") (pinfunction "IN_1") (pintype "power_in"))
    )
    (net (code "70") (name "Net-(J1-C2)") (class "Default")
      (node (ref "C17") (pin "2") (pinfunction "2_2") (pintype "passive"))
      (node (ref "C53") (pin "2") (pinfunction "2_2") (pintype "passive"))
      (node (ref "CN6") (pin "2") (pinfunction "2_2") (pintype "passive"))
      (node (ref "J1") (pin "2") (pinfunction "C2_2") (pintype "passive"))
    )
    (net (code "71") (name "Net-(J2-C2)") (class "Default")
      (node (ref "C73") (pin "2") (pinfunction "2_2") (pintype "passive"))
      (node (ref "C74") (pin "2") (pinfunction "2_2") (pintype "passive"))
      (node (ref "CN3") (pin "6") (pinfunction "6_6") (pintype "passive"))
      (node (ref "CN4") (pin "2") (pinfunction "2_2") (pintype "passive"))
      (node (ref "J2") (pin "2") (pinfunction "C2_2") (pintype "passive"))
    )
    (net (code "72") (name "Net-(L1-Pri+)") (class "Default")
      (node (ref "C1") (pin "1") (pinfunction "1_1") (pintype "passive"))
      (node (ref "CN2") (pin "1") (pinfunction "1_1") (pintype "passive"))
      (node (ref "L1") (pin "1") (pinfunction "Pri+_1") (pintype "passive"))
      (node (ref "MOV1") (pin "2") (pinfunction "2_2") (pintype "passive"))
    )
    (net (code "73") (name "Net-(L1-Pri-)") (class "Default")
      (node (ref "C2") (pin "1") (pinfunction "1_1") (pintype "passive"))
      (node (ref "C4") (pin "2") (pinfunction "2_2") (pintype "passive"))
      (node (ref "L1") (pin "2") (pinfunction "Pri-_2") (pintype "passive"))
      (node (ref "L6") (pin "3") (pinfunction "Sec+_3") (pintype "passive"))
    )
    (net (code "74") (name "Net-(L1-Sec+)") (class "Default")
      (node (ref "C1") (pin "2") (pinfunction "2_2") (pintype "passive"))
      (node (ref "F1") (pin "2") (pinfunction "2_2") (pintype "passive"))
      (node (ref "L1") (pin "3") (pinfunction "Sec+_3") (pintype "passive"))
      (node (ref "MOV1") (pin "1") (pinfunction "1_1") (pintype "passive"))
    )
    (net (code "75") (name "Net-(L1-Sec-)") (class "Default")
      (node (ref "C2") (pin "2") (pinfunction "2_2") (pintype "passive"))
      (node (ref "C3") (pin "2") (pinfunction "2_2") (pintype "passive"))
      (node (ref "L1") (pin "4") (pinfunction "Sec-_4") (pintype "passive"))
      (node (ref "L6") (pin "1") (pinfunction "Pri+_1") (pintype "passive"))
    )
    (net (code "76") (name "Net-(L2-Pri+)") (class "Default")
      (node (ref "C19") (pin "2") (pinfunction "2_2") (pintype "passive"))
      (node (ref "C75") (pin "2") (pinfunction "2_2") (pintype "passive"))
      (node (ref "F3") (pin "2") (pinfunction "2_2") (pintype "passive"))
      (node (ref "L2") (pin "1") (pinfunction "Pri+_1") (pintype "passive"))
    )
    (net (code "77") (name "Net-(L2-Pri-)") (class "Default")
      (node (ref "C76") (pin "2") (pinfunction "2_2") (pintype "passive"))
      (node (ref "L2") (pin "2") (pinfunction "Pri-_2") (pintype "passive"))
      (node (ref "NTC2") (pin "1") (pinfunction "1_1") (pintype "passive"))
    )
    (net (code "78") (name "Net-(L2-Sec-)") (class "Default")
      (node (ref "C76") (pin "1") (pinfunction "1_1") (pintype "passive"))
      (node (ref "D17") (pin "3") (pinfunction "C_3") (pintype "passive"))
      (node (ref "L2") (pin "4") (pinfunction "Sec-_4") (pintype "passive"))
    )
    (net (code "79") (name "Net-(LED1-A)") (class "Default")
      (node (ref "LED1") (pin "1") (pinfunction "A_1") (pintype "passive"))
      (node (ref "R26") (pin "1") (pinfunction "1_1") (pintype "passive"))
    )
    (net (code "80") (name "Net-(LED1-K)") (class "Default")
      (node (ref "LED1") (pin "2") (pinfunction "K_2") (pintype "passive"))
      (node (ref "U2") (pin "1") (pinfunction "A_1") (pintype "passive"))
    )
    (net (code "81") (name "Net-(LED3-A)") (class "Default")
      (node (ref "LED3") (pin "1") (pinfunction "A_1") (pintype "passive"))
      (node (ref "R75") (pin "1") (pinfunction "1_1") (pintype "passive"))
    )
    (net (code "82") (name "Net-(LED3-K)") (class "Default")
      (node (ref "LED3") (pin "2") (pinfunction "K_2") (pintype "passive"))
      (node (ref "U5") (pin "1") (pinfunction "A_1") (pintype "passive"))
    )
    (net (code "83") (name "Net-(Q1-B)") (class "Default")
      (node (ref "C28") (pin "2") (pinfunction "2_2") (pintype "passive"))
      (node (ref "Q1") (pin "1") (pinfunction "B_1") (pintype "passive"))
      (node (ref "R2") (pin "1") (pinfunction "1_1") (pintype "passive"))
    )
    (net (code "84") (name "Net-(Q1-E)") (class "Default")
      (node (ref "C29") (pin "2") (pinfunction "2_2") (pintype "passive"))
      (node (ref "Q1") (pin "2") (pinfunction "E_2") (pintype "passive"))
      (node (ref "R36") (pin "1") (pinfunction "1_1") (pintype "passive"))
      (node (ref "U6") (pin "1") (pinfunction "COMP_1") (pintype "passive"))
    )
    (net (code "85") (name "Net-(Q2-B)") (class "Default")
      (node (ref "Q2") (pin "3") (pinfunction "B_3") (pintype "passive"))
      (node (ref "Q3") (pin "3") (pinfunction "B_3") (pintype "passive"))
      (node (ref "R11") (pin "1") (pinfunction "1_1") (pintype "passive"))
    )
    (net (code "86") (name "Net-(Q2-E)") (class "Default")
      (node (ref "Q2") (pin "1") (pinfunction "E_1") (pintype "passive"))
      (node (ref "Q3") (pin "1") (pinfunction "E_1") (pintype "passive"))
      (node (ref "R12") (pin "2") (pinfunction "2_2") (pintype "passive"))
      (node (ref "R13") (pin "1") (pinfunction "1_1") (pintype "passive"))
    )
    (net (code "87") (name "Net-(Q3-C)") (class "Default")
      (node (ref "Q3") (pin "2") (pinfunction "C_2") (pintype "passive"))
      (node (ref "Q4") (pin "3") (pinfunction "S_3") (pintype "passive"))
      (node (ref "R14") (pin "1") (pinfunction "1_1") (pintype "passive"))
      (node (ref "R18") (pin "2") (pinfunction "2_2") (pintype "passive"))
      (node (ref "R25") (pin "2") (pinfunction "2_2") (pintype "passive"))
    )
    (net (code "88") (name "Net-(Q4-D)") (class "Default")
      (node (ref "D6") (pin "3") (pintype "passive"))
      (node (ref "L3") (pin "1") (pinfunction "1_1") (pintype "passive"))
      (node (ref "Q4") (pin "2") (pinfunction "D_2") (pintype "passive"))
    )
    (net (code "89") (name "Net-(Q5-B)") (class "Default")
      (node (ref "Q5") (pin "3") (pinfunction "B_3") (pintype "passive"))
      (node (ref "Q6") (pin "3") (pinfunction "B_3") (pintype "passive"))
      (node (ref "R21") (pin "1") (pinfunction "1_1") (pintype "passive"))
    )
    (net (code "90") (name "Net-(Q5-E)") (class "Default")
      (node (ref "Q5") (pin "1") (pinfunction "E_1") (pintype "passive"))
      (node (ref "Q6") (pin "1") (pinfunction "E_1") (pintype "passive"))
      (node (ref "R22") (pin "2") (pinfunction "2_2") (pintype "passive"))
      (node (ref "R23") (pin "1") (pinfunction "1_1") (pintype "passive"))
    )
    (net (code "91") (name "Net-(Q6-C)") (class "Default")
      (node (ref "Q6") (pin "2") (pinfunction "C_2") (pintype "passive"))
      (node (ref "Q7") (pin "3") (pinfunction "S_3") (pintype "passive"))
      (node (ref "R24") (pin "1") (pinfunction "1_1") (pintype "passive"))
      (node (ref "R28") (pin "2") (pinfunction "2_2") (pintype "passive"))
      (node (ref "R35") (pin "2") (pinfunction "2_2") (pintype "passive"))
    )
    (net (code "92") (name "Net-(Q7-D)") (class "Default")
      (node (ref "D8") (pin "3") (pintype "passive"))
      (node (ref "L4") (pin "1") (pinfunction "1_1") (pintype "passive"))
      (node (ref "Q7") (pin "2") (pinfunction "D_2") (pintype "passive"))
    )
    (net (code "93") (name "Net-(Q8-B)") (class "Default")
      (node (ref "Q8") (pin "3") (pinfunction "B_3") (pintype "passive"))
      (node (ref "Q9") (pin "3") (pinfunction "B_3") (pintype "passive"))
      (node (ref "R31") (pin "1") (pinfunction "1_1") (pintype "passive"))
    )
    (net (code "94") (name "Net-(Q8-E)") (class "Default")
      (node (ref "Q8") (pin "1") (pinfunction "E_1") (pintype "passive"))
      (node (ref "Q9") (pin "1") (pinfunction "E_1") (pintype "passive"))
      (node (ref "R32") (pin "2") (pinfunction "2_2") (pintype "passive"))
      (node (ref "R33") (pin "1") (pinfunction "1_1") (pintype "passive"))
    )
    (net (code "95") (name "Net-(Q10-D)") (class "Default")
      (node (ref "D10") (pin "3") (pintype "passive"))
      (node (ref "L5") (pin "1") (pinfunction "1_1") (pintype "passive"))
      (node (ref "Q10") (pin "2") (pinfunction "D_2") (pintype "passive"))
    )
    (net (code "96") (name "Net-(Q10-S)") (class "Default")
      (node (ref "Q10") (pin "3") (pinfunction "S_3") (pintype "passive"))
      (node (ref "Q9") (pin "2") (pinfunction "C_2") (pintype "passive"))
      (node (ref "R34") (pin "1") (pinfunction "1_1") (pintype "passive"))
      (node (ref "R38") (pin "2") (pinfunction "2_2") (pintype "passive"))
      (node (ref "R45") (pin "2") (pinfunction "2_2") (pintype "passive"))
    )
    (net (code "97") (name "Net-(Q11-B)") (class "Default")
      (node (ref "C67") (pin "2") (pinfunction "2_2") (pintype "passive"))
      (node (ref "Q11") (pin "1") (pinfunction "B_1") (pintype "passive"))
      (node (ref "R46") (pin "2") (pinfunction "2_2") (pintype "passive"))
      (node (ref "U6") (pin "4") (pinfunction "RT/CT_4") (pintype "passive"))
    )
    (net (code "98") (name "Net-(Q11-E)") (class "Default")
      (node (ref "Q11") (pin "2") (pinfunction "E_2") (pintype "passive"))
      (node (ref "R40") (pin "2") (pinfunction "2_2") (pintype "passive"))
    )
    (net (code "99") (name "Net-(Q13-S)") (class "Default")
      (node (ref "Q13") (pin "3") (pinfunction "S_3") (pintype "passive"))
      (node (ref "R79") (pin "2") (pinfunction "2_2") (pintype "passive"))
      (node (ref "R81") (pin "2") (pinfunction "2_2") (pintype "passive"))
      (node (ref "R83") (pin "1") (pinfunction "1_1") (pintype "passive"))
    )
    (net (code "100") (name "Net-(Q14-B)") (class "Default")
      (node (ref "C24") (pin "1") (pinfunction "1_1") (pintype "passive"))
      (node (ref "Q14") (pin "1") (pinfunction "B_1") (pintype "passive"))
      (node (ref "R43") (pin "2") (pinfunction "2_2") (pintype "passive"))
      (node (ref "R49") (pin "1") (pinfunction "1_1") (pintype "passive"))
    )
    (net (code "101") (name "Net-(Q14-C)") (class "Default")
      (node (ref "Q14") (pin "3") (pinfunction "C_3") (pintype "passive"))
      (node (ref "U2") (pin "2") (pinfunction "K_2") (pintype "passive"))
    )
    (net (code "102") (name "Net-(Q16-B)") (class "Default")
      (node (ref "C51") (pin "1") (pinfunction "1_1") (pintype "passive"))
      (node (ref "Q16") (pin "1") (pinfunction "B_1") (pintype "passive"))
      (node (ref "R91") (pin "2") (pinfunction "2_2") (pintype "passive"))
      (node (ref "R92") (pin "1") (pinfunction "1_1") (pintype "passive"))
    )
    (net (code "103") (name "Net-(Q16-C)") (class "Default")
      (node (ref "Q16") (pin "3") (pinfunction "C_3") (pintype "passive"))
      (node (ref "U5") (pin "2") (pinfunction "K_2") (pintype "passive"))
    )
    (net (code "104") (name "Net-(Q17-B)") (class "Default")
      (node (ref "C10") (pin "2") (pinfunction "2_2") (pintype "passive"))
      (node (ref "Q17") (pin "3") (pinfunction "B_3") (pintype "passive"))
      (node (ref "R48") (pin "2") (pinfunction "2_2") (pintype "passive"))
      (node (ref "U2") (pin "3") (pinfunction "E_3") (pintype "passive"))
    )
    (net (code "105") (name "Net-(Q18-B)") (class "Default")
      (node (ref "C23") (pin "1") (pinfunction "1_1") (pintype "passive"))
      (node (ref "Q18") (pin "1") (pinfunction "B_1") (pintype "passive"))
      (node (ref "R93") (pin "1") (pinfunction "1_1") (pintype "passive"))
      (node (ref "U5") (pin "3") (pinfunction "E_3") (pintype "passive"))
    )
    (net (code "106") (name "Net-(R1-Pad2)") (class "Default")
      (node (ref "R1") (pin "2") (pinfunction "2_2") (pintype "passive"))
      (node (ref "R4") (pin "2") (pinfunction "2_2") (pintype "passive"))
    )
    (net (code "107") (name "Net-(R5-Pad1)") (class "Default")
      (node (ref "R5") (pin "1") (pinfunction "1_1") (pintype "passive"))
      (node (ref "R6") (pin "2") (pinfunction "2_2") (pintype "passive"))
    )
    (net (code "108") (name "Net-(R7-Pad1)") (class "Default")
      (node (ref "R7") (pin "1") (pinfunction "1_1") (pintype "passive"))
      (node (ref "R7A") (pin "2") (pinfunction "2_2") (pintype "passive"))
    )
    (net (code "109") (name "Net-(R10-Pad1)") (class "Default")
      (node (ref "R10") (pin "1") (pinfunction "1_1") (pintype "passive"))
      (node (ref "R20") (pin "2") (pinfunction "2_2") (pintype "passive"))
    )
    (net (code "110") (name "Net-(R47-Pad1)") (class "Default")
      (node (ref "R47") (pin "1") (pinfunction "1_1") (pintype "passive"))
      (node (ref "R47A") (pin "1") (pinfunction "1_1") (pintype "passive"))
      (node (ref "R47B") (pin "1") (pinfunction "1_1") (pintype "passive"))
      (node (ref "T1") (pin "4") (pintype "passive"))
    )
    (net (code "111") (name "Net-(R56-Pad1)") (class "Default")
      (node (ref "R56") (pin "1") (pinfunction "1_1") (pintype "passive"))
      (node (ref "R56A") (pin "2") (pinfunction "2_2") (pintype "passive"))
    )
    (net (code "112") (name "Net-(R56-Pad2)") (class "Default")
      (node (ref "R56") (pin "2") (pinfunction "2_2") (pintype "passive"))
      (node (ref "R7A") (pin "1") (pinfunction "1_1") (pintype "passive"))
      (node (ref "R8") (pin "2") (pinfunction "2_2") (pintype "passive"))
    )
    (net (code "113") (name "Net-(U2-C)") (class "Default")
      (node (ref "R41") (pin "1") (pinfunction "1_1") (pintype "passive"))
      (node (ref "U2") (pin "4") (pinfunction "C_4") (pintype "passive"))
    )
    (net (code "114") (name "Net-(U4-GC)") (class "Default")
      (node (ref "C64") (pin "2") (pinfunction "2_2") (pintype "passive"))
      (node (ref "R58") (pin "1") (pinfunction "1_1") (pintype "passive"))
      (node (ref "U4") (pin "4") (pinfunction "GC_4") (pintype "passive"))
    )
    (net (code "115") (name "Net-(U4-LPK)") (class "Default")
      (node (ref "R61") (pin "1") (pinfunction "1_1") (pintype "passive"))
      (node (ref "U4") (pin "8") (pinfunction "LPK_8") (pintype "passive"))
    )
    (net (code "116") (name "Net-(U4-LS)") (class "Default")
      (node (ref "C63") (pin "2") (pinfunction "2_2") (pintype "passive"))
      (node (ref "R69") (pin "2") (pinfunction "2_2") (pintype "passive"))
      (node (ref "R69A") (pin "2") (pinfunction "2_2") (pintype "passive"))
      (node (ref "U4") (pin "17") (pinfunction "LS_17") (pintype "passive"))
    )
    (net (code "117") (name "Net-(U4-PVO)") (class "Default")
      (node (ref "R70") (pin "2") (pinfunction "2_2") (pintype "passive"))
      (node (ref "U4") (pin "2") (pinfunction "PVO_2") (pintype "passive"))
    )
    (net (code "118") (name "Net-(U4-RDZ)") (class "Default")
      (node (ref "C44") (pin "2") (pinfunction "2_2") (pintype "passive"))
      (node (ref "U4") (pin "9") (pinfunction "RDZ_9") (pintype "passive"))
    )
    (net (code "119") (name "Net-(U4-RLPK)") (class "Default")
      (node (ref "C62") (pin "2") (pinfunction "2_2") (pintype "passive"))
      (node (ref "R73") (pin "1") (pinfunction "1_1") (pintype "passive"))
      (node (ref "U4") (pin "6") (pinfunction "RLPK_6") (pintype "passive"))
    )
    (net (code "120") (name "Net-(U4-SS)") (class "Default")
      (node (ref "C37") (pin "2") (pinfunction "2_2") (pintype "passive"))
      (node (ref "U4") (pin "31") (pinfunction "SS_31") (pintype "passive"))
    )
    (net (code "121") (name "Net-(U5-C)") (class "Default")
      (node (ref "R80") (pin "2") (pinfunction "2_2") (pintype "passive"))
      (node (ref "U5") (pin "4") (pinfunction "C_4") (pintype "passive"))
    )
    (net (code "122") (name "Net-(U6-VFB)") (class "Default")
      (node (ref "C29") (pin "1") (pinfunction "1_1") (pintype "passive"))
      (node (ref "R36") (pin "2") (pinfunction "2_2") (pintype "passive"))
      (node (ref "R37") (pin "1") (pinfunction "1_1") (pintype "passive"))
      (node (ref "U6") (pin "2") (pinfunction "VFB_2") (pintype "passive"))
    )
    (net (code "123") (name "Net-(U7-A)") (class "Default")
      (node (ref "R82") (pin "1") (pinfunction "1_1") (pintype "passive"))
      (node (ref "R85") (pin "1") (pinfunction "1_1") (pintype "passive"))
      (node (ref "U7") (pin "1") (pinfunction "A_1") (pintype "passive"))
    )
    (net (code "124") (name "Net-(U202-K)") (class "Default")
      (node (ref "C70") (pin "1") (pinfunction "1_1") (pintype "passive"))
      (node (ref "R85") (pin "2") (pinfunction "2_2") (pintype "passive"))
      (node (ref "R87") (pin "1") (pinfunction "1_1") (pintype "passive"))
      (node (ref "U202") (pin "1") (pinfunction "K_1") (pintype "passive"))
      (node (ref "U7") (pin "2") (pinfunction "K_2") (pintype "passive"))
    )
    (net (code "125") (name "Net-(U202-REF)") (class "Default")
      (node (ref "C70") (pin "2") (pinfunction "2_2") (pintype "passive"))
      (node (ref "C72") (pin "2") (pinfunction "2_2") (pintype "passive"))
      (node (ref "R76") (pin "2") (pinfunction "2_2") (pintype "passive"))
      (node (ref "R84") (pin "1") (pinfunction "1_1") (pintype "passive"))
      (node (ref "R88") (pin "2") (pinfunction "2_2") (pintype "passive"))
      (node (ref "U202") (pin "8") (pinfunction "REF_8") (pintype "input"))
    )
    (net (code "126") (name "Null") (class "Default")
      (node (ref "C5") (pin "1") (pinfunction "1_1") (pintype "passive"))
      (node (ref "C78") (pin "2") (pinfunction "2_2") (pintype "passive"))
      (node (ref "CN8") (pin "1") (pinfunction "1_1") (pintype "passive"))
      (node (ref "D14") (pin "1") (pinfunction "A_1") (pintype "passive"))
      (node (ref "L6") (pin "4") (pinfunction "Sec-_4") (pintype "passive"))
    )
    (net (code "127") (name "OPFC1") (class "Default")
      (node (ref "R11") (pin "2") (pinfunction "2_2") (pintype "passive"))
      (node (ref "TP4") (pin "1") (pintype "passive"))
      (node (ref "U4") (pin "27") (pinfunction "OPFC1_27") (pintype "passive"))
    )
    (net (code "128") (name "OPFC2") (class "Default")
      (node (ref "R21") (pin "2") (pinfunction "2_2") (pintype "passive"))
      (node (ref "TP3") (pin "1") (pintype "passive"))
      (node (ref "U4") (pin "26") (pinfunction "OPFC2_26") (pintype "passive"))
    )
    (net (code "129") (name "OPFC3") (class "Default")
      (node (ref "R31") (pin "2") (pinfunction "2_2") (pintype "passive"))
      (node (ref "TP2") (pin "1") (pintype "passive"))
      (node (ref "U4") (pin "25") (pinfunction "OPFC3_25") (pintype "passive"))
    )
    (net (code "130") (name "PFC-EN") (class "Default")
      (node (ref "CN3") (pin "2") (pinfunction "2_2") (pintype "passive"))
      (node (ref "R91") (pin "1") (pinfunction "1_1") (pintype "passive"))
    )
    (net (code "131") (name "PGND") (class "Default")
      (node (ref "C10") (pin "1") (pinfunction "1_1") (pintype "passive"))
      (node (ref "C11") (pin "1") (pinfunction "1_1") (pintype "passive"))
      (node (ref "C12") (pin "2") (pinfunction "-_2") (pintype "passive"))
      (node (ref "C13") (pin "2") (pinfunction "2_2") (pintype "passive"))
      (node (ref "C14") (pin "1") (pinfunction "1_1") (pintype "passive"))
      (node (ref "C15") (pin "2") (pinfunction "2_2") (pintype "passive"))
      (node (ref "C16") (pin "1") (pinfunction "1_1") (pintype "passive"))
      (node (ref "C18") (pin "2") (pinfunction "2_2") (pintype "passive"))
      (node (ref "C22") (pin "2") (pinfunction "2_2") (pintype "passive"))
      (node (ref "C23") (pin "2") (pinfunction "2_2") (pintype "passive"))
      (node (ref "C25") (pin "2") (pinfunction "2_2") (pintype "passive"))
      (node (ref "C28") (pin "1") (pinfunction "1_1") (pintype "passive"))
      (node (ref "C32") (pin "2") (pinfunction "-_2") (pintype "passive"))
      (node (ref "C33") (pin "1") (pinfunction "1_1") (pintype "passive"))
      (node (ref "C34") (pin "2") (pinfunction "2_2") (pintype "passive"))
      (node (ref "C35") (pin "1") (pinfunction "1_1") (pintype "passive"))
      (node (ref "C36") (pin "1") (pinfunction "1_1") (pintype "passive"))
      (node (ref "C37") (pin "1") (pinfunction "1_1") (pintype "passive"))
      (node (ref "C38") (pin "1") (pinfunction "1_1") (pintype "passive"))
      (node (ref "C39") (pin "1") (pinfunction "1_1") (pintype "passive"))
      (node (ref "C41") (pin "1") (pinfunction "1_1") (pintype "passive"))
      (node (ref "C42") (pin "1") (pinfunction "1_1") (pintype "passive"))
      (node (ref "C43") (pin "1") (pinfunction "1_1") (pintype "passive"))
      (node (ref "C44") (pin "1") (pinfunction "1_1") (pintype "passive"))
      (node (ref "C46") (pin "1") (pinfunction "1_1") (pintype "passive"))
      (node (ref "C48") (pin "1") (pinfunction "1_1") (pintype "passive"))
      (node (ref "C50") (pin "1") (pinfunction "1_1") (pintype "passive"))
      (node (ref "C54") (pin "1") (pinfunction "1_1") (pintype "passive"))
      (node (ref "C55") (pin "2") (pinfunction "2_2") (pintype "passive"))
      (node (ref "C56") (pin "2") (pinfunction "2_2") (pintype "passive"))
      (node (ref "C57") (pin "2") (pinfunction "2_2") (pintype "passive"))
      (node (ref "C58") (pin "2") (pinfunction "2_2") (pintype "passive"))
      (node (ref "C59") (pin "2") (pinfunction "2_2") (pintype "passive"))
      (node (ref "C60") (pin "2") (pinfunction "2_2") (pintype "passive"))
      (node (ref "C62") (pin "1") (pinfunction "1_1") (pintype "passive"))
      (node (ref "C63") (pin "1") (pinfunction "1_1") (pintype "passive"))
      (node (ref "C64") (pin "1") (pinfunction "1_1") (pintype "passive"))
      (node (ref "C65") (pin "1") (pinfunction "1_1") (pintype "passive"))
      (node (ref "C66") (pin "1") (pinfunction "1_1") (pintype "passive"))
      (node (ref "C67") (pin "1") (pinfunction "1_1") (pintype "passive"))
      (node (ref "C68") (pin "2") (pinfunction "2_2") (pintype "passive"))
      (node (ref "C68A") (pin "2") (pinfunction "2_2") (pintype "passive"))
      (node (ref "C69") (pin "1") (pinfunction "1_1") (pintype "passive"))
      (node (ref "C71") (pin "1") (pinfunction "1_1") (pintype "passive"))
      (node (ref "C75") (pin "1") (pinfunction "1_1") (pintype "passive"))
      (node (ref "C77") (pin "1") (pinfunction "1_1") (pintype "passive"))
      (node (ref "C8") (pin "2") (pinfunction "2_2") (pintype "passive"))
      (node (ref "C9") (pin "2") (pinfunction "2_2") (pintype "passive"))
      (node (ref "CN10") (pin "1") (pinfunction "1_1") (pintype "passive"))
      (node (ref "CN5") (pin "3") (pinfunction "3_3") (pintype "passive"))
      (node (ref "D17") (pin "4") (pinfunction "A_4") (pintype "passive"))
      (node (ref "D5") (pin "1") (pinfunction "A_1") (pintype "passive"))
      (node (ref "L2") (pin "3") (pinfunction "Sec+_3") (pintype "passive"))
      (node (ref "MOV3") (pin "2") (pinfunction "2_2") (pintype "passive"))
      (node (ref "Q1") (pin "3") (pinfunction "C_3") (pintype "passive"))
      (node (ref "Q17") (pin "1") (pinfunction "E_1") (pintype "passive"))
      (node (ref "Q18") (pin "2") (pinfunction "E_2") (pintype "passive"))
      (node (ref "R19") (pin "2") (pinfunction "2_2") (pintype "passive"))
      (node (ref "R25") (pin "1") (pinfunction "1_1") (pintype "passive"))
      (node (ref "R29") (pin "2") (pinfunction "2_2") (pintype "passive"))
      (node (ref "R30") (pin "2") (pinfunction "2_2") (pintype "passive"))
      (node (ref "R35") (pin "1") (pinfunction "1_1") (pintype "passive"))
      (node (ref "R39") (pin "2") (pinfunction "2_2") (pintype "passive"))
      (node (ref "R45") (pin "1") (pinfunction "1_1") (pintype "passive"))
      (node (ref "R48") (pin "1") (pinfunction "1_1") (pintype "passive"))
      (node (ref "R52") (pin "1") (pinfunction "1_1") (pintype "passive"))
      (node (ref "R52A") (pin "1") (pinfunction "1_1") (pintype "passive"))
      (node (ref "R55") (pin "2") (pinfunction "2_2") (pintype "passive"))
      (node (ref "R55A") (pin "2") (pinfunction "2_2") (pintype "passive"))
      (node (ref "R57") (pin "2") (pinfunction "2_2") (pintype "passive"))
      (node (ref "R58") (pin "2") (pinfunction "2_2") (pintype "passive"))
      (node (ref "R59") (pin "2") (pinfunction "2_2") (pintype "passive"))
      (node (ref "R60") (pin "2") (pinfunction "2_2") (pintype "passive"))
      (node (ref "R60A") (pin "2") (pinfunction "2_2") (pintype "passive"))
      (node (ref "R62") (pin "1") (pinfunction "1_1") (pintype "passive"))
      (node (ref "R63") (pin "1") (pinfunction "1_1") (pintype "passive"))
      (node (ref "R64") (pin "1") (pinfunction "1_1") (pintype "passive"))
      (node (ref "R65") (pin "1") (pinfunction "1_1") (pintype "passive"))
      (node (ref "R66") (pin "1") (pinfunction "1_1") (pintype "passive"))
      (node (ref "R67") (pin "1") (pinfunction "1_1") (pintype "passive"))
      (node (ref "R68") (pin "1") (pinfunction "1_1") (pintype "passive"))
      (node (ref "R69") (pin "1") (pinfunction "1_1") (pintype "passive"))
      (node (ref "R69A") (pin "1") (pinfunction "1_1") (pintype "passive"))
      (node (ref "R70") (pin "1") (pinfunction "1_1") (pintype "passive"))
      (node (ref "R72") (pin "1") (pinfunction "1_1") (pintype "passive"))
      (node (ref "R73") (pin "2") (pinfunction "2_2") (pintype "passive"))
      (node (ref "R83") (pin "2") (pinfunction "2_2") (pintype "passive"))
      (node (ref "R86") (pin "1") (pinfunction "1_1") (pintype "passive"))
      (node (ref "R89") (pin "1") (pinfunction "1_1") (pintype "passive"))
      (node (ref "R93") (pin "2") (pinfunction "2_2") (pintype "passive"))
      (node (ref "T1") (pin "5") (pintype "passive"))
      (node (ref "TP1") (pin "1") (pintype "passive"))
      (node (ref "U1") (pin "2") (pinfunction "GND_2") (pintype "power_in"))
      (node (ref "U4") (pin "24") (pinfunction "GND_24") (pintype "passive"))
      (node (ref "U6") (pin "5") (pinfunction "GND_5") (pintype "passive"))
      (node (ref "ZD1") (pin "1") (pinfunction "A_1") (pintype "passive"))
    )
    (net (code "132") (name "Relay-Inrush") (class "Default")
      (node (ref "CN3") (pin "3") (pinfunction "3_3") (pintype "passive"))
      (node (ref "R43") (pin "1") (pinfunction "1_1") (pintype "passive"))
    )
    (net (code "133") (name "VCC") (class "Default")
      (node (ref "C65") (pin "2") (pinfunction "2_2") (pintype "passive"))
      (node (ref "C68") (pin "1") (pinfunction "1_1") (pintype "passive"))
      (node (ref "D21") (pin "2") (pinfunction "K_2") (pintype "passive"))
      (node (ref "R77") (pin "2") (pinfunction "2_2") (pintype "passive"))
      (node (ref "U6") (pin "7") (pinfunction "VCC_7") (pintype "passive"))
      (node (ref "ZD1") (pin "2") (pinfunction "K_2") (pintype "passive"))
    )
    (net (code "134") (name "VFB") (class "Default")
      (node (ref "C71") (pin "2") (pinfunction "2_2") (pintype "passive"))
      (node (ref "R37") (pin "2") (pinfunction "2_2") (pintype "passive"))
      (node (ref "R86") (pin "2") (pinfunction "2_2") (pintype "passive"))
      (node (ref "U7") (pin "3") (pinfunction "E_3") (pintype "passive"))
    )
    (net (code "135") (name "VRef") (class "Default")
      (node (ref "C66") (pin "2") (pinfunction "2_2") (pintype "passive"))
      (node (ref "Q11") (pin "3") (pinfunction "C_3") (pintype "passive"))
      (node (ref "R2") (pin "2") (pinfunction "2_2") (pintype "passive"))
      (node (ref "R46") (pin "1") (pinfunction "1_1") (pintype "passive"))
      (node (ref "U6") (pin "8") (pinfunction "VRef_8") (pintype "passive"))
      (node (ref "U7") (pin "4") (pinfunction "C_4") (pintype "passive"))
    )
    (net (code "136") (name "unconnected-(CN3-Pad1)") (class "Default")
      (node (ref "CN3") (pin "1") (pinfunction "1_1") (pintype "passive"))
    )
    (net (code "137") (name "unconnected-(CN5-Pad2)") (class "Default")
      (node (ref "CN5") (pin "2") (pinfunction "2_2") (pintype "passive"))
    )
    (net (code "138") (name "unconnected-(CN5-Pad4)") (class "Default")
      (node (ref "CN5") (pin "4") (pinfunction "4_4") (pintype "passive"))
    )
    (net (code "139") (name "unconnected-(HS1-Pad1)") (class "Default")
      (node (ref "HS1") (pin "1") (pintype "passive"))
    )
    (net (code "140") (name "unconnected-(HS2-Pad1)") (class "Default")
      (node (ref "HS2") (pin "1") (pintype "passive"))
    )
    (net (code "141") (name "unconnected-(HS3-Pad1)") (class "Default")
      (node (ref "HS3") (pin "1") (pintype "passive"))
    )
    (net (code "142") (name "unconnected-(P1-2-Pad1)") (class "Default")
      (node (ref "P1") (pin "1") (pinfunction "2_1") (pintype "passive"))
    )
    (net (code "143") (name "unconnected-(U202-NC-Pad4)") (class "Default")
      (node (ref "U202") (pin "4") (pinfunction "NC_4") (pintype "passive"))
    )
    (net (code "144") (name "unconnected-(U202-NC-Pad5)") (class "Default")
      (node (ref "U202") (pin "5") (pinfunction "NC_5") (pintype "passive"))
    )
  )
)
